# 32KRAM.net
KiCad netlist of a schematic drawn in EAGLE
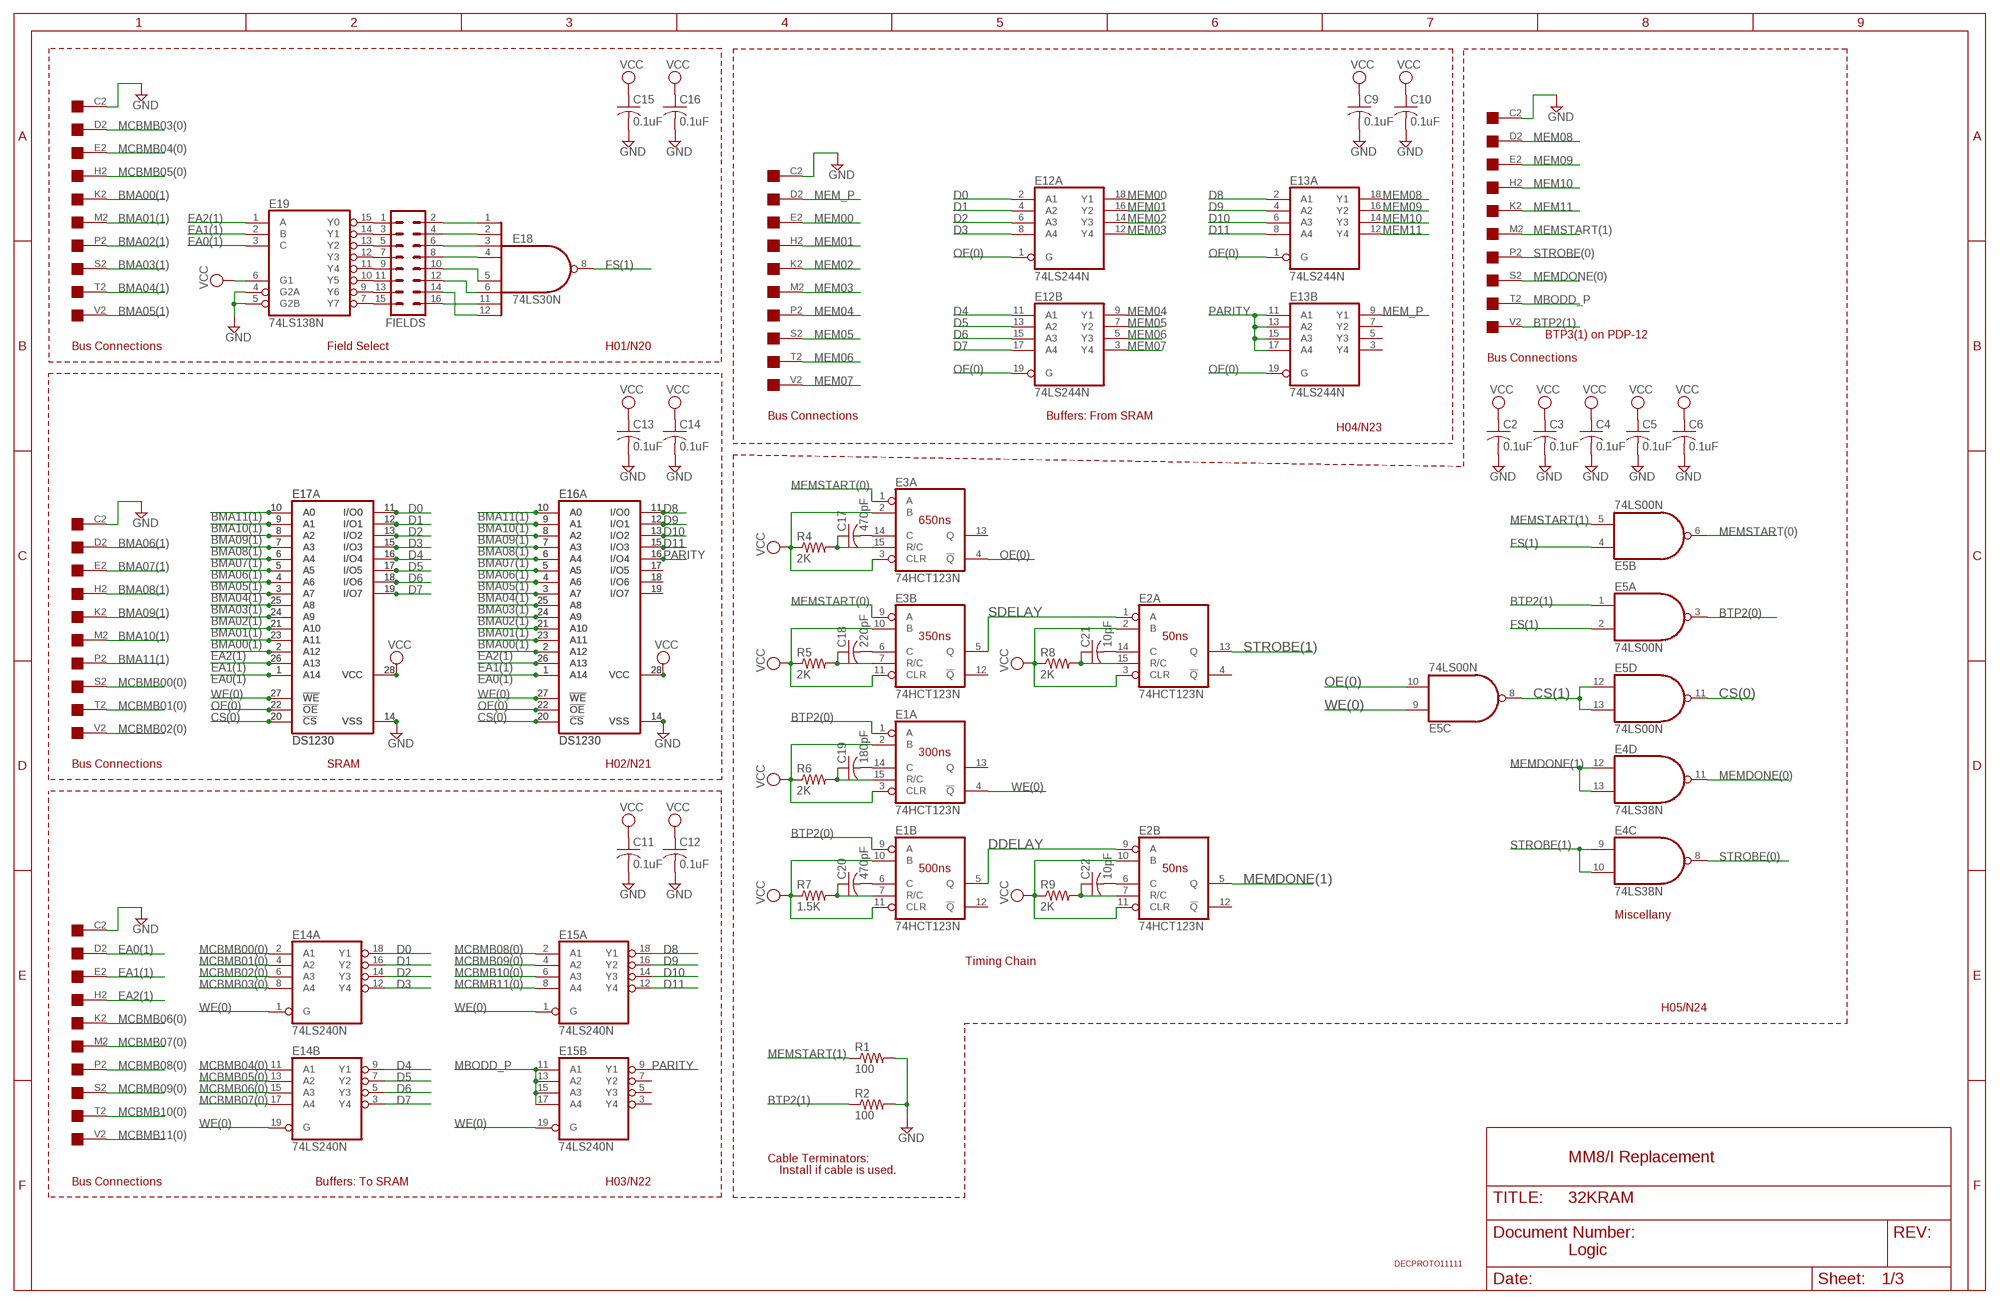
[diagram p0: schematic, sheet 1]
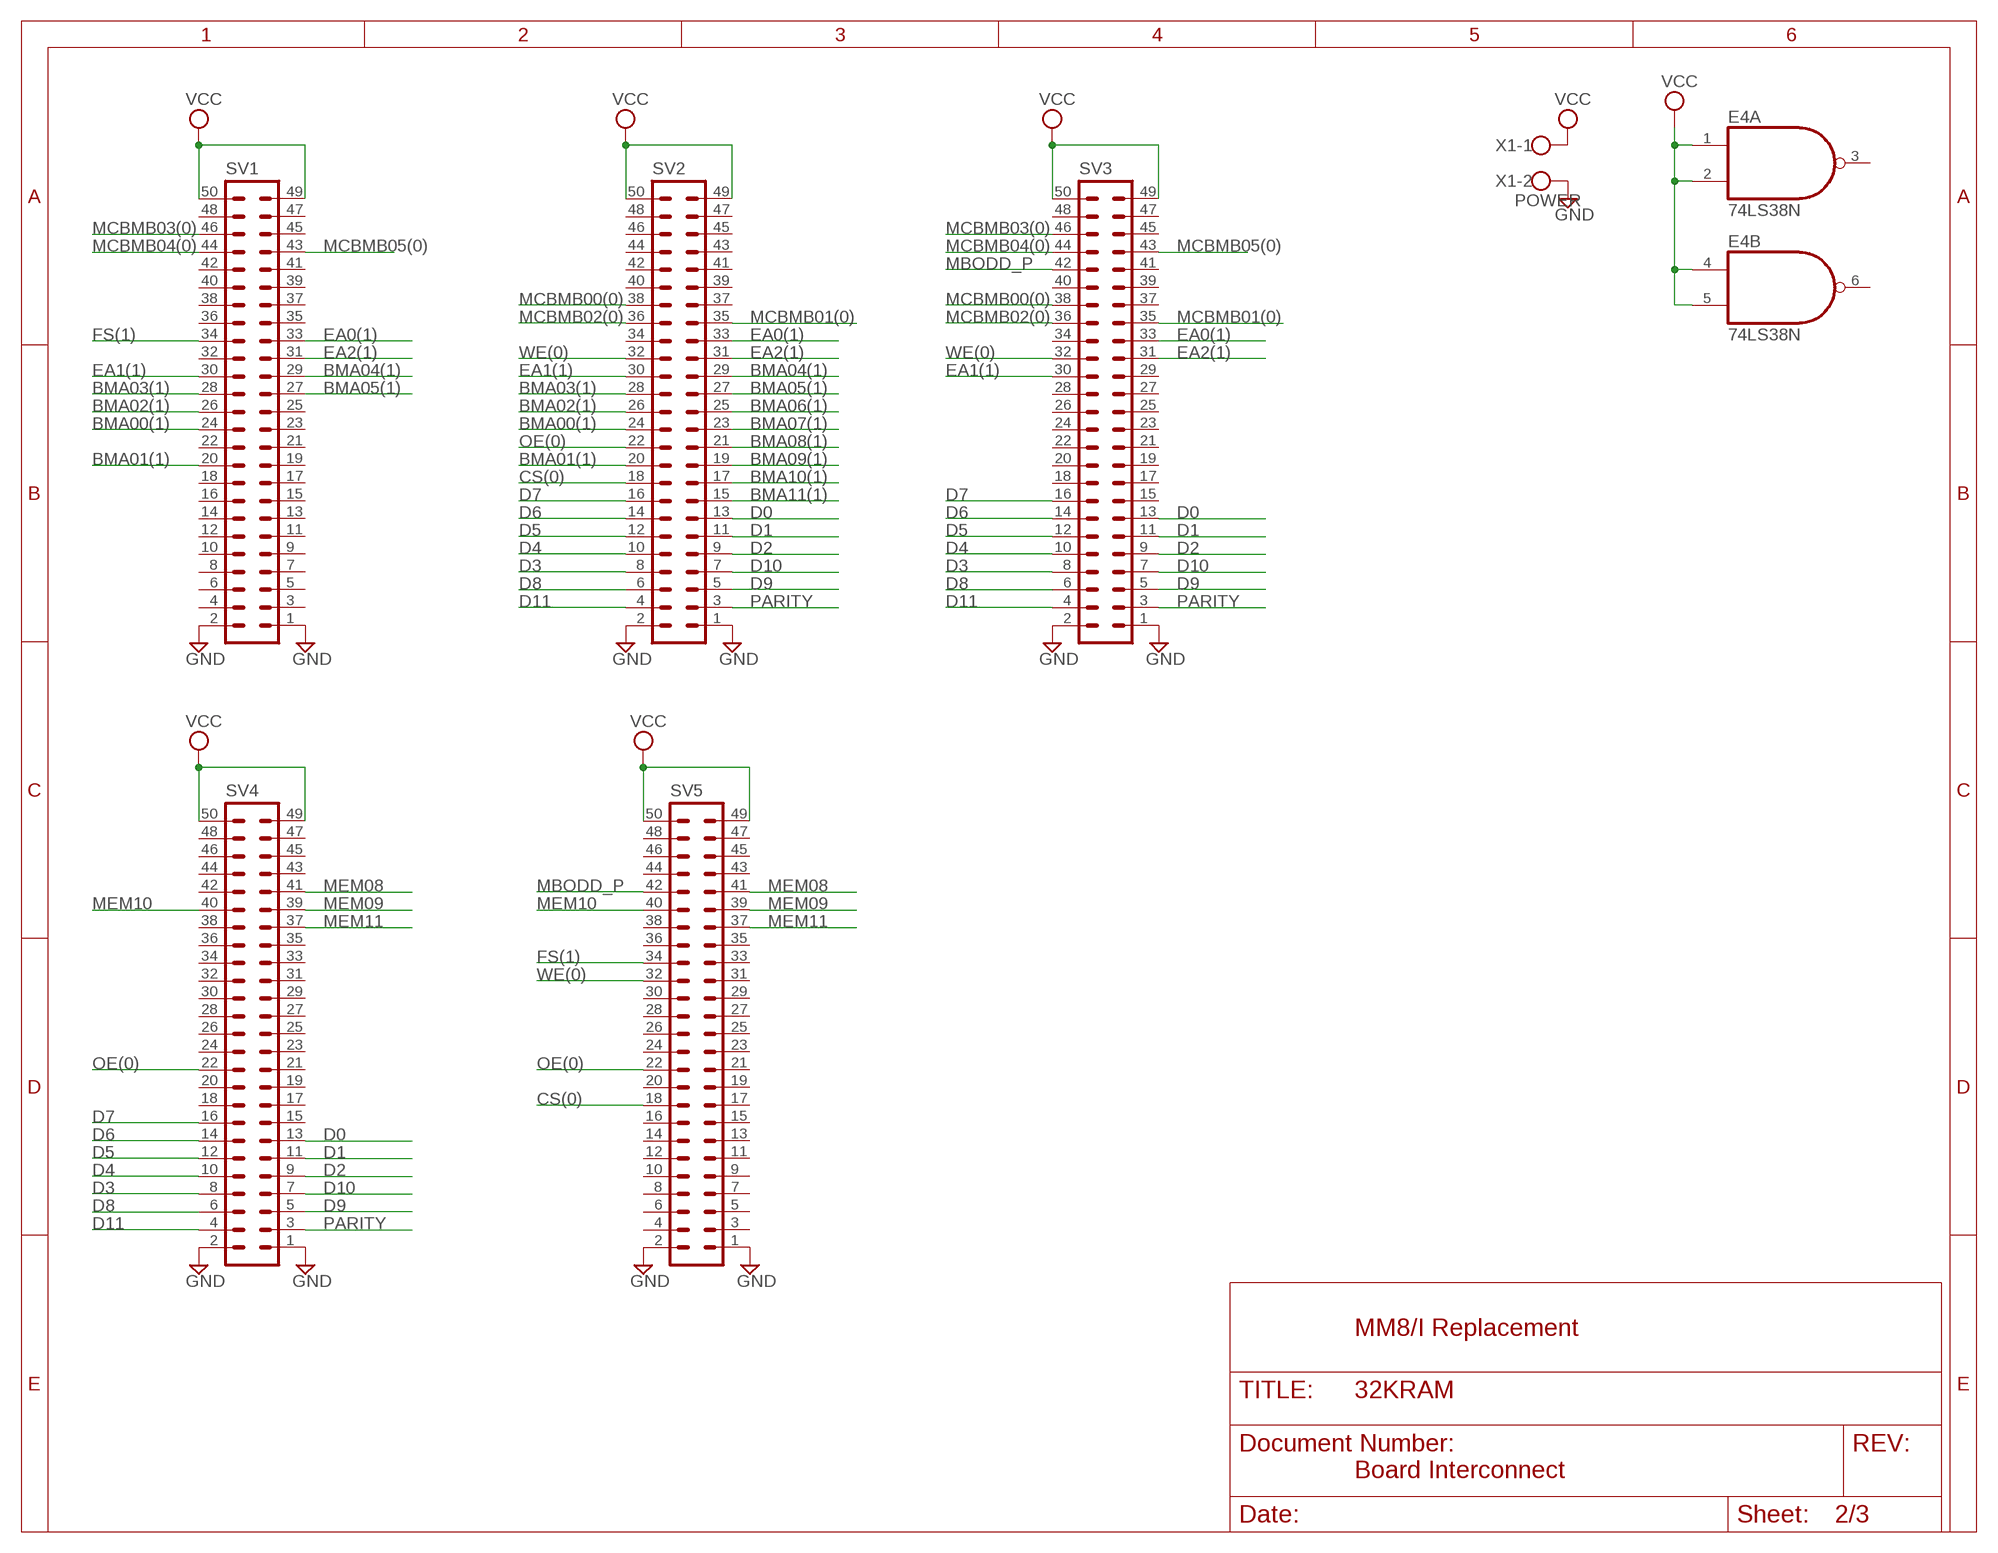
[diagram p1: schematic, sheet 2]
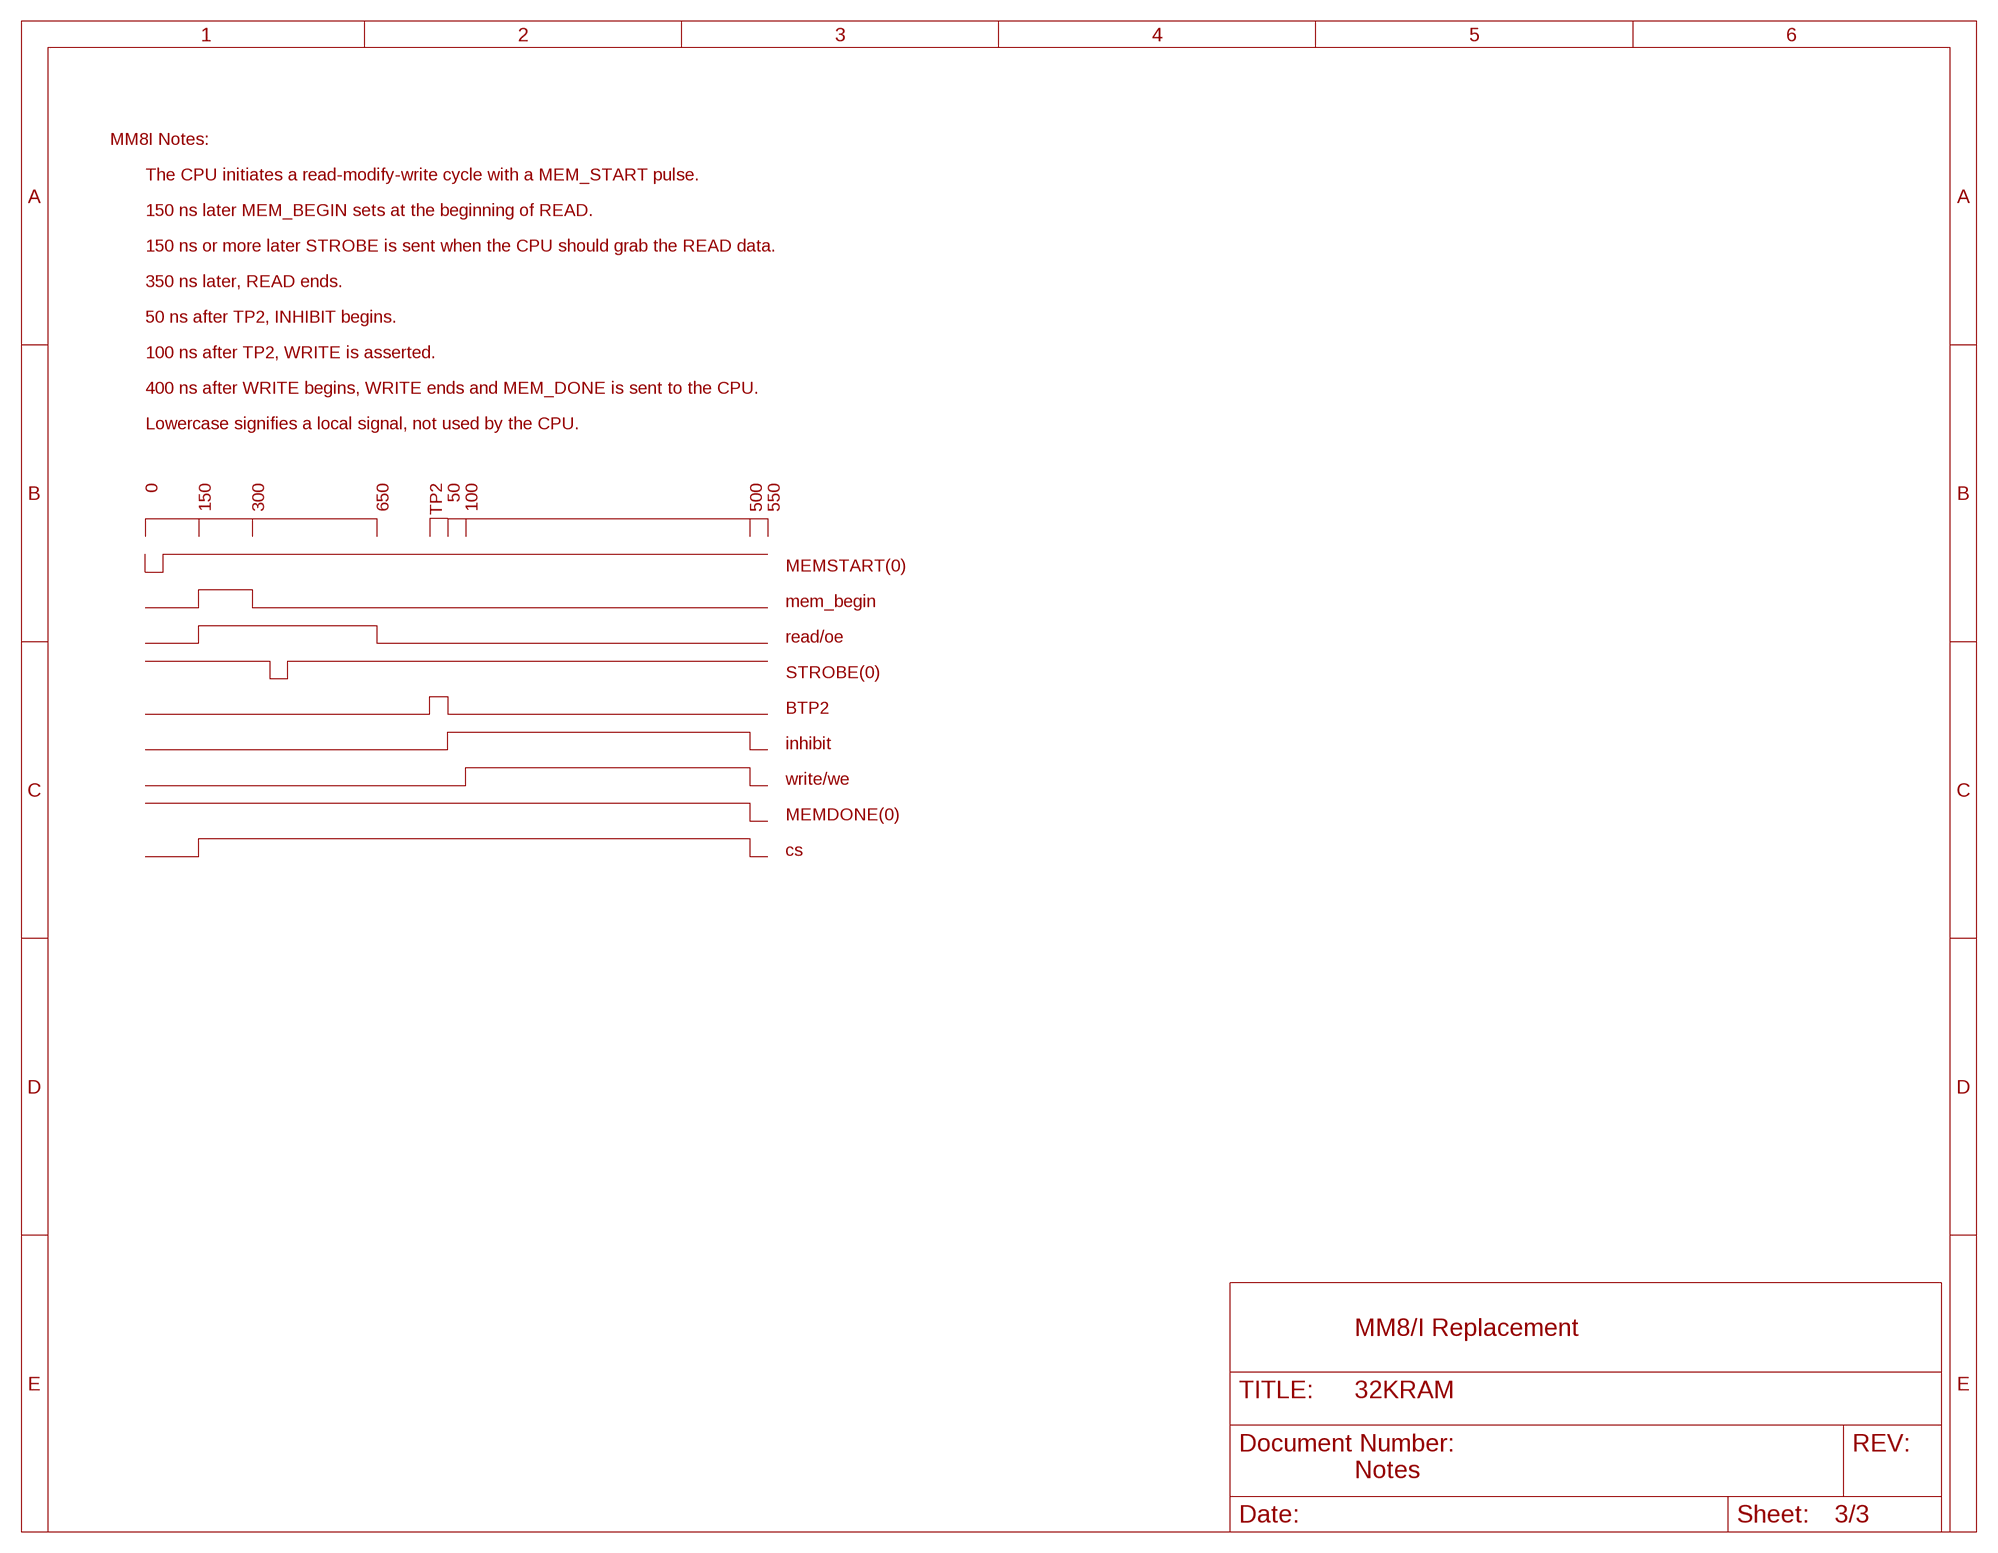
[diagram p2: schematic, sheet 3]

(export (version "E")
  (design (tool "Eeschema 10.0.6"))
  (components
    (comp (ref "E4")
      (value "74LS38N")
      (footprint "eagle-import:DIL14")
      (libsource (lib "eagle-import") (part "7438NLS"))
    )
    (comp (ref "SV1")
      (value "ML50L")
      (footprint "eagle-import:ML50L")
      (libsource (lib "eagle-import") (part "ML50L"))
    )
    (comp (ref "SV2")
      (value "ML50L")
      (footprint "eagle-import:ML50L")
      (libsource (lib "eagle-import") (part "ML50L"))
    )
    (comp (ref "SV3")
      (value "ML50L")
      (footprint "eagle-import:ML50L")
      (libsource (lib "eagle-import") (part "ML50L"))
    )
    (comp (ref "SV4")
      (value "ML50L")
      (footprint "eagle-import:ML50L")
      (libsource (lib "eagle-import") (part "ML50L"))
    )
    (comp (ref "SV5")
      (value "ML50L")
      (footprint "eagle-import:ML50L")
      (libsource (lib "eagle-import") (part "ML50L"))
    )
    (comp (ref "X1")
      (value "POWER")
      (footprint "eagle-import:W237-102")
      (fields (field (name "MPN") "237-102"))
      (libsource (lib "eagle-import") (part "W237-102"))
    )
    (comp (ref "C2")
      (value "0.1uF")
      (footprint "eagle-import:C050-025X075")
      (libsource (lib "eagle-import") (part "C-US050-025X075"))
    )
    (comp (ref "C3")
      (value "0.1uF")
      (footprint "eagle-import:C050-025X075")
      (libsource (lib "eagle-import") (part "C-US050-025X075"))
    )
    (comp (ref "C4")
      (value "0.1uF")
      (footprint "eagle-import:C050-025X075")
      (libsource (lib "eagle-import") (part "C-US050-025X075"))
    )
    (comp (ref "C5")
      (value "0.1uF")
      (footprint "eagle-import:C050-025X075")
      (libsource (lib "eagle-import") (part "C-US050-025X075"))
    )
    (comp (ref "C6")
      (value "0.1uF")
      (footprint "eagle-import:C050-025X075")
      (libsource (lib "eagle-import") (part "C-US050-025X075"))
    )
    (comp (ref "C9")
      (value "0.1uF")
      (footprint "eagle-import:C050-025X075")
      (libsource (lib "eagle-import") (part "C-US050-025X075"))
    )
    (comp (ref "C10")
      (value "0.1uF")
      (footprint "eagle-import:C050-025X075")
      (libsource (lib "eagle-import") (part "C-US050-025X075"))
    )
    (comp (ref "C11")
      (value "0.1uF")
      (footprint "eagle-import:C050-025X075")
      (libsource (lib "eagle-import") (part "C-US050-025X075"))
    )
    (comp (ref "C12")
      (value "0.1uF")
      (footprint "eagle-import:C050-025X075")
      (libsource (lib "eagle-import") (part "C-US050-025X075"))
    )
    (comp (ref "C13")
      (value "0.1uF")
      (footprint "eagle-import:C050-025X075")
      (libsource (lib "eagle-import") (part "C-US050-025X075"))
    )
    (comp (ref "C14")
      (value "0.1uF")
      (footprint "eagle-import:C050-025X075")
      (libsource (lib "eagle-import") (part "C-US050-025X075"))
    )
    (comp (ref "C15")
      (value "0.1uF")
      (footprint "eagle-import:C050-025X075")
      (libsource (lib "eagle-import") (part "C-US050-025X075"))
    )
    (comp (ref "C16")
      (value "0.1uF")
      (footprint "eagle-import:C050-025X075")
      (libsource (lib "eagle-import") (part "C-US050-025X075"))
    )
    (comp (ref "C17")
      (value "470pF")
      (footprint "eagle-import:C050-025X075")
      (libsource (lib "eagle-import") (part "C-US050-025X075"))
    )
    (comp (ref "C18")
      (value "220pF")
      (footprint "eagle-import:C050-025X075")
      (libsource (lib "eagle-import") (part "C-US050-025X075"))
    )
    (comp (ref "C19")
      (value "180pF")
      (footprint "eagle-import:C050-025X075")
      (libsource (lib "eagle-import") (part "C-US050-025X075"))
    )
    (comp (ref "C20")
      (value "470pF")
      (footprint "eagle-import:C050-025X075")
      (libsource (lib "eagle-import") (part "C-US050-025X075"))
    )
    (comp (ref "C21")
      (value "10pF")
      (footprint "eagle-import:C050-025X075")
      (libsource (lib "eagle-import") (part "C-US050-025X075"))
    )
    (comp (ref "C22")
      (value "10pF")
      (footprint "eagle-import:C050-025X075")
      (libsource (lib "eagle-import") (part "C-US050-025X075"))
    )
    (comp (ref "E1")
      (value "74HCT123N")
      (footprint "eagle-import:DIL16")
      (libsource (lib "eagle-import") (part "74123NLS"))
    )
    (comp (ref "E2")
      (value "74HCT123N")
      (footprint "eagle-import:DIL16")
      (libsource (lib "eagle-import") (part "74123NLS"))
    )
    (comp (ref "E3")
      (value "74HCT123N")
      (footprint "eagle-import:DIL16")
      (libsource (lib "eagle-import") (part "74123NLS"))
    )
    (comp (ref "E5")
      (value "74LS00N")
      (footprint "eagle-import:DIL14")
      (libsource (lib "eagle-import") (part "7400NLS"))
    )
    (comp (ref "E12")
      (value "74LS244N")
      (footprint "eagle-import:DIL20")
      (libsource (lib "eagle-import") (part "74244NS"))
    )
    (comp (ref "E13")
      (value "74LS244N")
      (footprint "eagle-import:DIL20")
      (libsource (lib "eagle-import") (part "74244NS"))
    )
    (comp (ref "E14")
      (value "74LS240N")
      (footprint "eagle-import:DIL20")
      (libsource (lib "eagle-import") (part "74240NS"))
    )
    (comp (ref "E15")
      (value "74LS240N")
      (footprint "eagle-import:DIL20")
      (libsource (lib "eagle-import") (part "74240NS"))
    )
    (comp (ref "E16")
      (value "DS1230")
      (footprint "eagle-import:DIL28-6")
      (libsource (lib "eagle-import") (part "62256P"))
    )
    (comp (ref "E16A")
      (value "DS1230")
      (footprint "eagle-import:DIL28-3")
      (libsource (lib "eagle-import") (part "62832P"))
    )
    (comp (ref "E17")
      (value "DS1230")
      (footprint "eagle-import:DIL28-6")
      (libsource (lib "eagle-import") (part "62256P"))
    )
    (comp (ref "E17A")
      (value "DS1230")
      (footprint "eagle-import:DIL28-3")
      (libsource (lib "eagle-import") (part "62832P"))
    )
    (comp (ref "E18")
      (value "74LS30N")
      (footprint "eagle-import:DIL14")
      (libsource (lib "eagle-import") (part "7430NLS"))
    )
    (comp (ref "E19")
      (value "74LS138N")
      (footprint "eagle-import:DIL16")
      (libsource (lib "eagle-import") (part "74138NLS"))
    )
    (comp (ref "FIELDS")
      (value "MA08-2")
      (footprint "eagle-import:MA08-2")
      (libsource (lib "eagle-import") (part "MA08-2"))
    )
    (comp (ref "H01")
      (value "EDGE-1")
      (footprint "eagle-import:EDGE-CON1")
      (libsource (lib "eagle-import") (part "EDGE-1"))
    )
    (comp (ref "H02")
      (value "EDGE-1")
      (footprint "eagle-import:EDGE-CON1")
      (libsource (lib "eagle-import") (part "EDGE-1"))
    )
    (comp (ref "H03")
      (value "EDGE-1")
      (footprint "eagle-import:EDGE-CON1")
      (libsource (lib "eagle-import") (part "EDGE-1"))
    )
    (comp (ref "H04")
      (value "EDGE-1")
      (footprint "eagle-import:EDGE-CON1")
      (libsource (lib "eagle-import") (part "EDGE-1"))
    )
    (comp (ref "H05")
      (value "EDGE-1")
      (footprint "eagle-import:EDGE-CON1")
      (libsource (lib "eagle-import") (part "EDGE-1"))
    )
    (comp (ref "R1")
      (value "100")
      (footprint "eagle-import:0207_10")
      (libsource (lib "eagle-import") (part "R-US_0207/10"))
    )
    (comp (ref "R2")
      (value "100")
      (footprint "eagle-import:0207_10")
      (libsource (lib "eagle-import") (part "R-US_0207/10"))
    )
    (comp (ref "R4")
      (value "2K")
      (footprint "eagle-import:0207_10")
      (libsource (lib "eagle-import") (part "R-US_0207/10"))
    )
    (comp (ref "R5")
      (value "2K")
      (footprint "eagle-import:0207_10")
      (libsource (lib "eagle-import") (part "R-US_0207/10"))
    )
    (comp (ref "R6")
      (value "2K")
      (footprint "eagle-import:0207_10")
      (libsource (lib "eagle-import") (part "R-US_0207/10"))
    )
    (comp (ref "R7")
      (value "1.5K")
      (footprint "eagle-import:0207_10")
      (libsource (lib "eagle-import") (part "R-US_0207/10"))
    )
    (comp (ref "R8")
      (value "2K")
      (footprint "eagle-import:0207_10")
      (libsource (lib "eagle-import") (part "R-US_0207/10"))
    )
    (comp (ref "R9")
      (value "2K")
      (footprint "eagle-import:0207_10")
      (libsource (lib "eagle-import") (part "R-US_0207/10"))
    )
    (comp (ref "U$6")
      (value "DECPROTO11111")
      (footprint "eagle-import:DECPROTO11111")
      (libsource (lib "eagle-import") (part "DECPROTO11111"))
    )
  )
  (nets
    (net (code "1") (name "BMA00(1)") (class "Default")
      (node (ref "E16") (pin "23") (pinfunction "A11_23") (pintype "input"))
      (node (ref "E16A") (pin "23") (pinfunction "A11_23") (pintype "input"))
      (node (ref "E17") (pin "23") (pinfunction "A11_23") (pintype "input"))
      (node (ref "E17A") (pin "23") (pinfunction "A11_23") (pintype "input"))
      (node (ref "H01") (pin "K2") (pinfunction "1_K2") (pintype "bidirectional"))
      (node (ref "SV1") (pin "24") (pinfunction "24_24") (pintype "passive"))
      (node (ref "SV2") (pin "24") (pinfunction "24_24") (pintype "passive"))
    )
    (net (code "2") (name "BMA01(1)") (class "Default")
      (node (ref "E16") (pin "21") (pinfunction "A10_21") (pintype "input"))
      (node (ref "E16A") (pin "21") (pinfunction "A10_21") (pintype "input"))
      (node (ref "E17") (pin "21") (pinfunction "A10_21") (pintype "input"))
      (node (ref "E17A") (pin "21") (pinfunction "A10_21") (pintype "input"))
      (node (ref "H01") (pin "M2") (pinfunction "1_M2") (pintype "bidirectional"))
      (node (ref "SV1") (pin "20") (pinfunction "20_20") (pintype "passive"))
      (node (ref "SV2") (pin "20") (pinfunction "20_20") (pintype "passive"))
    )
    (net (code "3") (name "BMA02(1)") (class "Default")
      (node (ref "E16") (pin "24") (pinfunction "A9_24") (pintype "input"))
      (node (ref "E16A") (pin "24") (pinfunction "A9_24") (pintype "input"))
      (node (ref "E17") (pin "24") (pinfunction "A9_24") (pintype "input"))
      (node (ref "E17A") (pin "24") (pinfunction "A9_24") (pintype "input"))
      (node (ref "H01") (pin "P2") (pinfunction "1_P2") (pintype "bidirectional"))
      (node (ref "SV1") (pin "26") (pinfunction "26_26") (pintype "passive"))
      (node (ref "SV2") (pin "26") (pinfunction "26_26") (pintype "passive"))
    )
    (net (code "4") (name "BMA03(1)") (class "Default")
      (node (ref "E16") (pin "25") (pinfunction "A8_25") (pintype "input"))
      (node (ref "E16A") (pin "25") (pinfunction "A8_25") (pintype "input"))
      (node (ref "E17") (pin "25") (pinfunction "A8_25") (pintype "input"))
      (node (ref "E17A") (pin "25") (pinfunction "A8_25") (pintype "input"))
      (node (ref "H01") (pin "S2") (pinfunction "1_S2") (pintype "bidirectional"))
      (node (ref "SV1") (pin "28") (pinfunction "28_28") (pintype "passive"))
      (node (ref "SV2") (pin "28") (pinfunction "28_28") (pintype "passive"))
    )
    (net (code "5") (name "BMA04(1)") (class "Default")
      (node (ref "E16") (pin "3") (pinfunction "A7_3") (pintype "input"))
      (node (ref "E16A") (pin "3") (pinfunction "A7_3") (pintype "input"))
      (node (ref "E17") (pin "3") (pinfunction "A7_3") (pintype "input"))
      (node (ref "E17A") (pin "3") (pinfunction "A7_3") (pintype "input"))
      (node (ref "H01") (pin "T2") (pinfunction "1_T2") (pintype "bidirectional"))
      (node (ref "SV1") (pin "29") (pinfunction "29_29") (pintype "passive"))
      (node (ref "SV2") (pin "29") (pinfunction "29_29") (pintype "passive"))
    )
    (net (code "6") (name "BMA05(1)") (class "Default")
      (node (ref "E16") (pin "4") (pinfunction "A6_4") (pintype "input"))
      (node (ref "E16A") (pin "4") (pinfunction "A6_4") (pintype "input"))
      (node (ref "E17") (pin "4") (pinfunction "A6_4") (pintype "input"))
      (node (ref "E17A") (pin "4") (pinfunction "A6_4") (pintype "input"))
      (node (ref "H01") (pin "V2") (pinfunction "1_V2") (pintype "bidirectional"))
      (node (ref "SV1") (pin "27") (pinfunction "27_27") (pintype "passive"))
      (node (ref "SV2") (pin "27") (pinfunction "27_27") (pintype "passive"))
    )
    (net (code "7") (name "BMA06(1)") (class "Default")
      (node (ref "E16") (pin "5") (pinfunction "A5_5") (pintype "input"))
      (node (ref "E16A") (pin "5") (pinfunction "A5_5") (pintype "input"))
      (node (ref "E17") (pin "5") (pinfunction "A5_5") (pintype "input"))
      (node (ref "E17A") (pin "5") (pinfunction "A5_5") (pintype "input"))
      (node (ref "H02") (pin "D2") (pinfunction "1_D2") (pintype "bidirectional"))
      (node (ref "SV2") (pin "25") (pinfunction "25_25") (pintype "passive"))
    )
    (net (code "8") (name "BMA07(1)") (class "Default")
      (node (ref "E16") (pin "6") (pinfunction "A4_6") (pintype "input"))
      (node (ref "E16A") (pin "6") (pinfunction "A4_6") (pintype "input"))
      (node (ref "E17") (pin "6") (pinfunction "A4_6") (pintype "input"))
      (node (ref "E17A") (pin "6") (pinfunction "A4_6") (pintype "input"))
      (node (ref "H02") (pin "E2") (pinfunction "1_E2") (pintype "bidirectional"))
      (node (ref "SV2") (pin "23") (pinfunction "23_23") (pintype "passive"))
    )
    (net (code "9") (name "BMA08(1)") (class "Default")
      (node (ref "E16") (pin "7") (pinfunction "A3_7") (pintype "input"))
      (node (ref "E16A") (pin "7") (pinfunction "A3_7") (pintype "input"))
      (node (ref "E17") (pin "7") (pinfunction "A3_7") (pintype "input"))
      (node (ref "E17A") (pin "7") (pinfunction "A3_7") (pintype "input"))
      (node (ref "H02") (pin "H2") (pinfunction "1_H2") (pintype "bidirectional"))
      (node (ref "SV2") (pin "21") (pinfunction "21_21") (pintype "passive"))
    )
    (net (code "10") (name "BMA09(1)") (class "Default")
      (node (ref "E16") (pin "8") (pinfunction "A2_8") (pintype "input"))
      (node (ref "E16A") (pin "8") (pinfunction "A2_8") (pintype "input"))
      (node (ref "E17") (pin "8") (pinfunction "A2_8") (pintype "input"))
      (node (ref "E17A") (pin "8") (pinfunction "A2_8") (pintype "input"))
      (node (ref "H02") (pin "K2") (pinfunction "1_K2") (pintype "bidirectional"))
      (node (ref "SV2") (pin "19") (pinfunction "19_19") (pintype "passive"))
    )
    (net (code "11") (name "BMA10(1)") (class "Default")
      (node (ref "E16") (pin "9") (pinfunction "A1_9") (pintype "input"))
      (node (ref "E16A") (pin "9") (pinfunction "A1_9") (pintype "input"))
      (node (ref "E17") (pin "9") (pinfunction "A1_9") (pintype "input"))
      (node (ref "E17A") (pin "9") (pinfunction "A1_9") (pintype "input"))
      (node (ref "H02") (pin "M2") (pinfunction "1_M2") (pintype "bidirectional"))
      (node (ref "SV2") (pin "17") (pinfunction "17_17") (pintype "passive"))
    )
    (net (code "12") (name "BMA11(1)") (class "Default")
      (node (ref "E16") (pin "10") (pinfunction "A0_10") (pintype "input"))
      (node (ref "E16A") (pin "10") (pinfunction "A0_10") (pintype "input"))
      (node (ref "E17") (pin "10") (pinfunction "A0_10") (pintype "input"))
      (node (ref "E17A") (pin "10") (pinfunction "A0_10") (pintype "input"))
      (node (ref "H02") (pin "P2") (pinfunction "1_P2") (pintype "bidirectional"))
      (node (ref "SV2") (pin "15") (pinfunction "15_15") (pintype "passive"))
    )
    (net (code "13") (name "BTP2(0)") (class "Default")
      (node (ref "E1") (pin "1") (pinfunction "A_1") (pintype "input"))
      (node (ref "E1") (pin "9") (pinfunction "A_9") (pintype "input"))
      (node (ref "E5") (pin "3") (pinfunction "O_3") (pintype "output"))
    )
    (net (code "14") (name "BTP2(1)") (class "Default")
      (node (ref "E5") (pin "1") (pinfunction "I0_1") (pintype "input"))
      (node (ref "H05") (pin "V2") (pinfunction "1_V2") (pintype "bidirectional"))
      (node (ref "R2") (pin "1") (pinfunction "1_1") (pintype "passive"))
    )
    (net (code "15") (name "CS(0)") (class "Default")
      (node (ref "E16") (pin "20") (pinfunction "~{CS}_20") (pintype "input"))
      (node (ref "E16A") (pin "20") (pinfunction "~{CS}_20") (pintype "input"))
      (node (ref "E17") (pin "20") (pinfunction "~{CS}_20") (pintype "input"))
      (node (ref "E17A") (pin "20") (pinfunction "~{CS}_20") (pintype "input"))
      (node (ref "E5") (pin "11") (pinfunction "O_11") (pintype "output"))
      (node (ref "SV2") (pin "18") (pinfunction "18_18") (pintype "passive"))
      (node (ref "SV5") (pin "18") (pinfunction "18_18") (pintype "passive"))
    )
    (net (code "16") (name "CS(1)") (class "Default")
      (node (ref "E5") (pin "12") (pinfunction "I0_12") (pintype "input"))
      (node (ref "E5") (pin "13") (pinfunction "I1_13") (pintype "input"))
      (node (ref "E5") (pin "8") (pinfunction "O_8") (pintype "output"))
    )
    (net (code "17") (name "D0") (class "Default")
      (node (ref "E12") (pin "2") (pinfunction "A1_2") (pintype "input"))
      (node (ref "E14") (pin "18") (pinfunction "Y1_18") (pintype "tri_state"))
      (node (ref "E17") (pin "11") (pinfunction "I/O0_11") (pintype "bidirectional"))
      (node (ref "E17A") (pin "11") (pinfunction "I/O0_11") (pintype "bidirectional"))
      (node (ref "SV2") (pin "13") (pinfunction "13_13") (pintype "passive"))
      (node (ref "SV3") (pin "13") (pinfunction "13_13") (pintype "passive"))
      (node (ref "SV4") (pin "13") (pinfunction "13_13") (pintype "passive"))
    )
    (net (code "18") (name "D1") (class "Default")
      (node (ref "E12") (pin "4") (pinfunction "A2_4") (pintype "input"))
      (node (ref "E14") (pin "16") (pinfunction "Y2_16") (pintype "tri_state"))
      (node (ref "E17") (pin "12") (pinfunction "I/O1_12") (pintype "bidirectional"))
      (node (ref "E17A") (pin "12") (pinfunction "I/O1_12") (pintype "bidirectional"))
      (node (ref "SV2") (pin "11") (pinfunction "11_11") (pintype "passive"))
      (node (ref "SV3") (pin "11") (pinfunction "11_11") (pintype "passive"))
      (node (ref "SV4") (pin "11") (pinfunction "11_11") (pintype "passive"))
    )
    (net (code "19") (name "D2") (class "Default")
      (node (ref "E12") (pin "6") (pinfunction "A3_6") (pintype "input"))
      (node (ref "E14") (pin "14") (pinfunction "Y3_14") (pintype "tri_state"))
      (node (ref "E17") (pin "13") (pinfunction "I/O2_13") (pintype "bidirectional"))
      (node (ref "E17A") (pin "13") (pinfunction "I/O2_13") (pintype "bidirectional"))
      (node (ref "SV2") (pin "9") (pinfunction "9_9") (pintype "passive"))
      (node (ref "SV3") (pin "9") (pinfunction "9_9") (pintype "passive"))
      (node (ref "SV4") (pin "9") (pinfunction "9_9") (pintype "passive"))
    )
    (net (code "20") (name "D3") (class "Default")
      (node (ref "E12") (pin "8") (pinfunction "A4_8") (pintype "input"))
      (node (ref "E14") (pin "12") (pinfunction "Y4_12") (pintype "tri_state"))
      (node (ref "E17") (pin "15") (pinfunction "I/O3_15") (pintype "bidirectional"))
      (node (ref "E17A") (pin "15") (pinfunction "I/O3_15") (pintype "bidirectional"))
      (node (ref "SV2") (pin "8") (pinfunction "8_8") (pintype "passive"))
      (node (ref "SV3") (pin "8") (pinfunction "8_8") (pintype "passive"))
      (node (ref "SV4") (pin "8") (pinfunction "8_8") (pintype "passive"))
    )
    (net (code "21") (name "D4") (class "Default")
      (node (ref "E12") (pin "11") (pinfunction "A1_11") (pintype "input"))
      (node (ref "E14") (pin "9") (pinfunction "Y1_9") (pintype "tri_state"))
      (node (ref "E17") (pin "16") (pinfunction "I/O4_16") (pintype "bidirectional"))
      (node (ref "E17A") (pin "16") (pinfunction "I/O4_16") (pintype "bidirectional"))
      (node (ref "SV2") (pin "10") (pinfunction "10_10") (pintype "passive"))
      (node (ref "SV3") (pin "10") (pinfunction "10_10") (pintype "passive"))
      (node (ref "SV4") (pin "10") (pinfunction "10_10") (pintype "passive"))
    )
    (net (code "22") (name "D5") (class "Default")
      (node (ref "E12") (pin "13") (pinfunction "A2_13") (pintype "input"))
      (node (ref "E14") (pin "7") (pinfunction "Y2_7") (pintype "tri_state"))
      (node (ref "E17") (pin "17") (pinfunction "I/O5_17") (pintype "bidirectional"))
      (node (ref "E17A") (pin "17") (pinfunction "I/O5_17") (pintype "bidirectional"))
      (node (ref "SV2") (pin "12") (pinfunction "12_12") (pintype "passive"))
      (node (ref "SV3") (pin "12") (pinfunction "12_12") (pintype "passive"))
      (node (ref "SV4") (pin "12") (pinfunction "12_12") (pintype "passive"))
    )
    (net (code "23") (name "D6") (class "Default")
      (node (ref "E12") (pin "15") (pinfunction "A3_15") (pintype "input"))
      (node (ref "E14") (pin "5") (pinfunction "Y3_5") (pintype "tri_state"))
      (node (ref "E17") (pin "18") (pinfunction "I/O6_18") (pintype "bidirectional"))
      (node (ref "E17A") (pin "18") (pinfunction "I/O6_18") (pintype "bidirectional"))
      (node (ref "SV2") (pin "14") (pinfunction "14_14") (pintype "passive"))
      (node (ref "SV3") (pin "14") (pinfunction "14_14") (pintype "passive"))
      (node (ref "SV4") (pin "14") (pinfunction "14_14") (pintype "passive"))
    )
    (net (code "24") (name "D7") (class "Default")
      (node (ref "E12") (pin "17") (pinfunction "A4_17") (pintype "input"))
      (node (ref "E14") (pin "3") (pinfunction "Y4_3") (pintype "tri_state"))
      (node (ref "E17") (pin "19") (pinfunction "I/O7_19") (pintype "bidirectional"))
      (node (ref "E17A") (pin "19") (pinfunction "I/O7_19") (pintype "bidirectional"))
      (node (ref "SV2") (pin "16") (pinfunction "16_16") (pintype "passive"))
      (node (ref "SV3") (pin "16") (pinfunction "16_16") (pintype "passive"))
      (node (ref "SV4") (pin "16") (pinfunction "16_16") (pintype "passive"))
    )
    (net (code "25") (name "D8") (class "Default")
      (node (ref "E13") (pin "2") (pinfunction "A1_2") (pintype "input"))
      (node (ref "E15") (pin "18") (pinfunction "Y1_18") (pintype "tri_state"))
      (node (ref "E16") (pin "11") (pinfunction "I/O0_11") (pintype "bidirectional"))
      (node (ref "E16A") (pin "11") (pinfunction "I/O0_11") (pintype "bidirectional"))
      (node (ref "SV2") (pin "6") (pinfunction "6_6") (pintype "passive"))
      (node (ref "SV3") (pin "6") (pinfunction "6_6") (pintype "passive"))
      (node (ref "SV4") (pin "6") (pinfunction "6_6") (pintype "passive"))
    )
    (net (code "26") (name "D9") (class "Default")
      (node (ref "E13") (pin "4") (pinfunction "A2_4") (pintype "input"))
      (node (ref "E15") (pin "16") (pinfunction "Y2_16") (pintype "tri_state"))
      (node (ref "E16") (pin "12") (pinfunction "I/O1_12") (pintype "bidirectional"))
      (node (ref "E16A") (pin "12") (pinfunction "I/O1_12") (pintype "bidirectional"))
      (node (ref "SV2") (pin "5") (pinfunction "5_5") (pintype "passive"))
      (node (ref "SV3") (pin "5") (pinfunction "5_5") (pintype "passive"))
      (node (ref "SV4") (pin "5") (pinfunction "5_5") (pintype "passive"))
    )
    (net (code "27") (name "D10") (class "Default")
      (node (ref "E13") (pin "6") (pinfunction "A3_6") (pintype "input"))
      (node (ref "E15") (pin "14") (pinfunction "Y3_14") (pintype "tri_state"))
      (node (ref "E16") (pin "13") (pinfunction "I/O2_13") (pintype "bidirectional"))
      (node (ref "E16A") (pin "13") (pinfunction "I/O2_13") (pintype "bidirectional"))
      (node (ref "SV2") (pin "7") (pinfunction "7_7") (pintype "passive"))
      (node (ref "SV3") (pin "7") (pinfunction "7_7") (pintype "passive"))
      (node (ref "SV4") (pin "7") (pinfunction "7_7") (pintype "passive"))
    )
    (net (code "28") (name "D11") (class "Default")
      (node (ref "E13") (pin "8") (pinfunction "A4_8") (pintype "input"))
      (node (ref "E15") (pin "12") (pinfunction "Y4_12") (pintype "tri_state"))
      (node (ref "E16") (pin "15") (pinfunction "I/O3_15") (pintype "bidirectional"))
      (node (ref "E16A") (pin "15") (pinfunction "I/O3_15") (pintype "bidirectional"))
      (node (ref "SV2") (pin "4") (pinfunction "4_4") (pintype "passive"))
      (node (ref "SV3") (pin "4") (pinfunction "4_4") (pintype "passive"))
      (node (ref "SV4") (pin "4") (pinfunction "4_4") (pintype "passive"))
    )
    (net (code "29") (name "DDELAY") (class "Default")
      (node (ref "E1") (pin "5") (pinfunction "Q_5") (pintype "output"))
      (node (ref "E2") (pin "9") (pinfunction "A_9") (pintype "input"))
    )
    (net (code "30") (name "EA0(1)") (class "Default")
      (node (ref "E16") (pin "1") (pinfunction "A14_1") (pintype "input"))
      (node (ref "E16A") (pin "1") (pinfunction "A14_1") (pintype "input"))
      (node (ref "E17") (pin "1") (pinfunction "A14_1") (pintype "input"))
      (node (ref "E17A") (pin "1") (pinfunction "A14_1") (pintype "input"))
      (node (ref "E19") (pin "3") (pinfunction "C_3") (pintype "input"))
      (node (ref "H03") (pin "D2") (pinfunction "1_D2") (pintype "bidirectional"))
      (node (ref "SV1") (pin "33") (pinfunction "33_33") (pintype "passive"))
      (node (ref "SV2") (pin "33") (pinfunction "33_33") (pintype "passive"))
      (node (ref "SV3") (pin "33") (pinfunction "33_33") (pintype "passive"))
    )
    (net (code "31") (name "EA1(1)") (class "Default")
      (node (ref "E16") (pin "26") (pinfunction "A13_26") (pintype "input"))
      (node (ref "E16A") (pin "26") (pinfunction "A13_26") (pintype "input"))
      (node (ref "E17") (pin "26") (pinfunction "A13_26") (pintype "input"))
      (node (ref "E17A") (pin "26") (pinfunction "A13_26") (pintype "input"))
      (node (ref "E19") (pin "2") (pinfunction "B_2") (pintype "input"))
      (node (ref "H03") (pin "E2") (pinfunction "1_E2") (pintype "bidirectional"))
      (node (ref "SV1") (pin "30") (pinfunction "30_30") (pintype "passive"))
      (node (ref "SV2") (pin "30") (pinfunction "30_30") (pintype "passive"))
      (node (ref "SV3") (pin "30") (pinfunction "30_30") (pintype "passive"))
    )
    (net (code "32") (name "EA2(1)") (class "Default")
      (node (ref "E16") (pin "2") (pinfunction "A12_2") (pintype "input"))
      (node (ref "E16A") (pin "2") (pinfunction "A12_2") (pintype "input"))
      (node (ref "E17") (pin "2") (pinfunction "A12_2") (pintype "input"))
      (node (ref "E17A") (pin "2") (pinfunction "A12_2") (pintype "input"))
      (node (ref "E19") (pin "1") (pinfunction "A_1") (pintype "input"))
      (node (ref "H03") (pin "H2") (pinfunction "1_H2") (pintype "bidirectional"))
      (node (ref "SV1") (pin "31") (pinfunction "31_31") (pintype "passive"))
      (node (ref "SV2") (pin "31") (pinfunction "31_31") (pintype "passive"))
      (node (ref "SV3") (pin "31") (pinfunction "31_31") (pintype "passive"))
    )
    (net (code "33") (name "FS(1)") (class "Default")
      (node (ref "E18") (pin "8") (pinfunction "O_8") (pintype "output"))
      (node (ref "E5") (pin "2") (pinfunction "I1_2") (pintype "input"))
      (node (ref "E5") (pin "4") (pinfunction "I0_4") (pintype "input"))
      (node (ref "SV1") (pin "34") (pinfunction "34_34") (pintype "passive"))
      (node (ref "SV5") (pin "34") (pinfunction "34_34") (pintype "passive"))
    )
    (net (code "34") (name "GND") (class "Default")
      (node (ref "C10") (pin "2") (pinfunction "2_2") (pintype "passive"))
      (node (ref "C11") (pin "2") (pinfunction "2_2") (pintype "passive"))
      (node (ref "C12") (pin "2") (pinfunction "2_2") (pintype "passive"))
      (node (ref "C13") (pin "2") (pinfunction "2_2") (pintype "passive"))
      (node (ref "C14") (pin "2") (pinfunction "2_2") (pintype "passive"))
      (node (ref "C15") (pin "2") (pinfunction "2_2") (pintype "passive"))
      (node (ref "C16") (pin "2") (pinfunction "2_2") (pintype "passive"))
      (node (ref "C2") (pin "2") (pinfunction "2_2") (pintype "passive"))
      (node (ref "C3") (pin "2") (pinfunction "2_2") (pintype "passive"))
      (node (ref "C4") (pin "2") (pinfunction "2_2") (pintype "passive"))
      (node (ref "C5") (pin "2") (pinfunction "2_2") (pintype "passive"))
      (node (ref "C6") (pin "2") (pinfunction "2_2") (pintype "passive"))
      (node (ref "C9") (pin "2") (pinfunction "2_2") (pintype "passive"))
      (node (ref "E16") (pin "14") (pinfunction "VSS_14") (pintype "power_in"))
      (node (ref "E16A") (pin "14") (pinfunction "VSS_14") (pintype "power_in"))
      (node (ref "E17") (pin "14") (pinfunction "VSS_14") (pintype "power_in"))
      (node (ref "E17A") (pin "14") (pinfunction "VSS_14") (pintype "power_in"))
      (node (ref "E19") (pin "4") (pinfunction "G2A_4") (pintype "input"))
      (node (ref "E19") (pin "5") (pinfunction "G2B_5") (pintype "input"))
      (node (ref "H01") (pin "C2") (pinfunction "1_C2") (pintype "bidirectional"))
      (node (ref "H02") (pin "C2") (pinfunction "1_C2") (pintype "bidirectional"))
      (node (ref "H03") (pin "C2") (pinfunction "1_C2") (pintype "bidirectional"))
      (node (ref "H04") (pin "C2") (pinfunction "1_C2") (pintype "bidirectional"))
      (node (ref "H05") (pin "C2") (pinfunction "1_C2") (pintype "bidirectional"))
      (node (ref "R1") (pin "2") (pinfunction "2_2") (pintype "passive"))
      (node (ref "R2") (pin "2") (pinfunction "2_2") (pintype "passive"))
      (node (ref "SV1") (pin "1") (pinfunction "1_1") (pintype "passive"))
      (node (ref "SV1") (pin "2") (pinfunction "2_2") (pintype "passive"))
      (node (ref "SV2") (pin "1") (pinfunction "1_1") (pintype "passive"))
      (node (ref "SV2") (pin "2") (pinfunction "2_2") (pintype "passive"))
      (node (ref "SV3") (pin "1") (pinfunction "1_1") (pintype "passive"))
      (node (ref "SV3") (pin "2") (pinfunction "2_2") (pintype "passive"))
      (node (ref "SV4") (pin "1") (pinfunction "1_1") (pintype "passive"))
      (node (ref "SV4") (pin "2") (pinfunction "2_2") (pintype "passive"))
      (node (ref "SV5") (pin "1") (pinfunction "1_1") (pintype "passive"))
      (node (ref "SV5") (pin "2") (pinfunction "2_2") (pintype "passive"))
      (node (ref "X1") (pin "2") (pinfunction "KL_2") (pintype "passive"))
    )
    (net (code "35") (name "MBODD_P") (class "Default")
      (node (ref "E15") (pin "11") (pinfunction "A1_11") (pintype "input"))
      (node (ref "E15") (pin "13") (pinfunction "A2_13") (pintype "input"))
      (node (ref "E15") (pin "15") (pinfunction "A3_15") (pintype "input"))
      (node (ref "E15") (pin "17") (pinfunction "A4_17") (pintype "input"))
      (node (ref "H05") (pin "T2") (pinfunction "1_T2") (pintype "bidirectional"))
      (node (ref "SV3") (pin "42") (pinfunction "42_42") (pintype "passive"))
      (node (ref "SV5") (pin "42") (pinfunction "42_42") (pintype "passive"))
    )
    (net (code "36") (name "MCBMB00(0)") (class "Default")
      (node (ref "E14") (pin "2") (pinfunction "A1_2") (pintype "input"))
      (node (ref "H02") (pin "S2") (pinfunction "1_S2") (pintype "bidirectional"))
      (node (ref "SV2") (pin "38") (pinfunction "38_38") (pintype "passive"))
      (node (ref "SV3") (pin "38") (pinfunction "38_38") (pintype "passive"))
    )
    (net (code "37") (name "MCBMB01(0)") (class "Default")
      (node (ref "E14") (pin "4") (pinfunction "A2_4") (pintype "input"))
      (node (ref "H02") (pin "T2") (pinfunction "1_T2") (pintype "bidirectional"))
      (node (ref "SV2") (pin "35") (pinfunction "35_35") (pintype "passive"))
      (node (ref "SV3") (pin "35") (pinfunction "35_35") (pintype "passive"))
    )
    (net (code "38") (name "MCBMB02(0)") (class "Default")
      (node (ref "E14") (pin "6") (pinfunction "A3_6") (pintype "input"))
      (node (ref "H02") (pin "V2") (pinfunction "1_V2") (pintype "bidirectional"))
      (node (ref "SV2") (pin "36") (pinfunction "36_36") (pintype "passive"))
      (node (ref "SV3") (pin "36") (pinfunction "36_36") (pintype "passive"))
    )
    (net (code "39") (name "MCBMB03(0)") (class "Default")
      (node (ref "E14") (pin "8") (pinfunction "A4_8") (pintype "input"))
      (node (ref "H01") (pin "D2") (pinfunction "1_D2") (pintype "bidirectional"))
      (node (ref "SV1") (pin "46") (pinfunction "46_46") (pintype "passive"))
      (node (ref "SV3") (pin "46") (pinfunction "46_46") (pintype "passive"))
    )
    (net (code "40") (name "MCBMB04(0)") (class "Default")
      (node (ref "E14") (pin "11") (pinfunction "A1_11") (pintype "input"))
      (node (ref "H01") (pin "E2") (pinfunction "1_E2") (pintype "bidirectional"))
      (node (ref "SV1") (pin "44") (pinfunction "44_44") (pintype "passive"))
      (node (ref "SV3") (pin "44") (pinfunction "44_44") (pintype "passive"))
    )
    (net (code "41") (name "MCBMB05(0)") (class "Default")
      (node (ref "E14") (pin "13") (pinfunction "A2_13") (pintype "input"))
      (node (ref "H01") (pin "H2") (pinfunction "1_H2") (pintype "bidirectional"))
      (node (ref "SV1") (pin "43") (pinfunction "43_43") (pintype "passive"))
      (node (ref "SV3") (pin "43") (pinfunction "43_43") (pintype "passive"))
    )
    (net (code "42") (name "MCBMB06(0)") (class "Default")
      (node (ref "E14") (pin "15") (pinfunction "A3_15") (pintype "input"))
      (node (ref "H03") (pin "K2") (pinfunction "1_K2") (pintype "bidirectional"))
    )
    (net (code "43") (name "MCBMB07(0)") (class "Default")
      (node (ref "E14") (pin "17") (pinfunction "A4_17") (pintype "input"))
      (node (ref "H03") (pin "M2") (pinfunction "1_M2") (pintype "bidirectional"))
    )
    (net (code "44") (name "MCBMB08(0)") (class "Default")
      (node (ref "E15") (pin "2") (pinfunction "A1_2") (pintype "input"))
      (node (ref "H03") (pin "P2") (pinfunction "1_P2") (pintype "bidirectional"))
    )
    (net (code "45") (name "MCBMB09(0)") (class "Default")
      (node (ref "E15") (pin "4") (pinfunction "A2_4") (pintype "input"))
      (node (ref "H03") (pin "S2") (pinfunction "1_S2") (pintype "bidirectional"))
    )
    (net (code "46") (name "MCBMB10(0)") (class "Default")
      (node (ref "E15") (pin "6") (pinfunction "A3_6") (pintype "input"))
      (node (ref "H03") (pin "T2") (pinfunction "1_T2") (pintype "bidirectional"))
    )
    (net (code "47") (name "MCBMB11(0)") (class "Default")
      (node (ref "E15") (pin "8") (pinfunction "A4_8") (pintype "input"))
      (node (ref "H03") (pin "V2") (pinfunction "1_V2") (pintype "bidirectional"))
    )
    (net (code "48") (name "MEM00") (class "Default")
      (node (ref "E12") (pin "18") (pinfunction "Y1_18") (pintype "tri_state"))
      (node (ref "H04") (pin "E2") (pinfunction "1_E2") (pintype "bidirectional"))
    )
    (net (code "49") (name "MEM01") (class "Default")
      (node (ref "E12") (pin "16") (pinfunction "Y2_16") (pintype "tri_state"))
      (node (ref "H04") (pin "H2") (pinfunction "1_H2") (pintype "bidirectional"))
    )
    (net (code "50") (name "MEM02") (class "Default")
      (node (ref "E12") (pin "14") (pinfunction "Y3_14") (pintype "tri_state"))
      (node (ref "H04") (pin "K2") (pinfunction "1_K2") (pintype "bidirectional"))
    )
    (net (code "51") (name "MEM03") (class "Default")
      (node (ref "E12") (pin "12") (pinfunction "Y4_12") (pintype "tri_state"))
      (node (ref "H04") (pin "M2") (pinfunction "1_M2") (pintype "bidirectional"))
    )
    (net (code "52") (name "MEM04") (class "Default")
      (node (ref "E12") (pin "9") (pinfunction "Y1_9") (pintype "tri_state"))
      (node (ref "H04") (pin "P2") (pinfunction "1_P2") (pintype "bidirectional"))
    )
    (net (code "53") (name "MEM05") (class "Default")
      (node (ref "E12") (pin "7") (pinfunction "Y2_7") (pintype "tri_state"))
      (node (ref "H04") (pin "S2") (pinfunction "1_S2") (pintype "bidirectional"))
    )
    (net (code "54") (name "MEM06") (class "Default")
      (node (ref "E12") (pin "5") (pinfunction "Y3_5") (pintype "tri_state"))
      (node (ref "H04") (pin "T2") (pinfunction "1_T2") (pintype "bidirectional"))
    )
    (net (code "55") (name "MEM07") (class "Default")
      (node (ref "E12") (pin "3") (pinfunction "Y4_3") (pintype "tri_state"))
      (node (ref "H04") (pin "V2") (pinfunction "1_V2") (pintype "bidirectional"))
    )
    (net (code "56") (name "MEM08") (class "Default")
      (node (ref "E13") (pin "18") (pinfunction "Y1_18") (pintype "tri_state"))
      (node (ref "H05") (pin "D2") (pinfunction "1_D2") (pintype "bidirectional"))
      (node (ref "SV4") (pin "41") (pinfunction "41_41") (pintype "passive"))
      (node (ref "SV5") (pin "41") (pinfunction "41_41") (pintype "passive"))
    )
    (net (code "57") (name "MEM09") (class "Default")
      (node (ref "E13") (pin "16") (pinfunction "Y2_16") (pintype "tri_state"))
      (node (ref "H05") (pin "E2") (pinfunction "1_E2") (pintype "bidirectional"))
      (node (ref "SV4") (pin "39") (pinfunction "39_39") (pintype "passive"))
      (node (ref "SV5") (pin "39") (pinfunction "39_39") (pintype "passive"))
    )
    (net (code "58") (name "MEM10") (class "Default")
      (node (ref "E13") (pin "14") (pinfunction "Y3_14") (pintype "tri_state"))
      (node (ref "H05") (pin "H2") (pinfunction "1_H2") (pintype "bidirectional"))
      (node (ref "SV4") (pin "40") (pinfunction "40_40") (pintype "passive"))
      (node (ref "SV5") (pin "40") (pinfunction "40_40") (pintype "passive"))
    )
    (net (code "59") (name "MEM11") (class "Default")
      (node (ref "E13") (pin "12") (pinfunction "Y4_12") (pintype "tri_state"))
      (node (ref "H05") (pin "K2") (pinfunction "1_K2") (pintype "bidirectional"))
      (node (ref "SV4") (pin "37") (pinfunction "37_37") (pintype "passive"))
      (node (ref "SV5") (pin "37") (pinfunction "37_37") (pintype "passive"))
    )
    (net (code "60") (name "MEMDONE(0)") (class "Default")
      (node (ref "E4") (pin "11") (pinfunction "O_11") (pintype "open_collector"))
      (node (ref "H05") (pin "S2") (pinfunction "1_S2") (pintype "bidirectional"))
    )
    (net (code "61") (name "MEMDONE(1)") (class "Default")
      (node (ref "E2") (pin "5") (pinfunction "Q_5") (pintype "output"))
      (node (ref "E4") (pin "12") (pinfunction "I0_12") (pintype "input"))
      (node (ref "E4") (pin "13") (pinfunction "I1_13") (pintype "input"))
    )
    (net (code "62") (name "MEMSTART(0)") (class "Default")
      (node (ref "E3") (pin "1") (pinfunction "A_1") (pintype "input"))
      (node (ref "E3") (pin "9") (pinfunction "A_9") (pintype "input"))
      (node (ref "E5") (pin "6") (pinfunction "O_6") (pintype "output"))
    )
    (net (code "63") (name "MEMSTART(1)") (class "Default")
      (node (ref "E5") (pin "5") (pinfunction "I1_5") (pintype "input"))
      (node (ref "H05") (pin "M2") (pinfunction "1_M2") (pintype "bidirectional"))
      (node (ref "R1") (pin "1") (pinfunction "1_1") (pintype "passive"))
    )
    (net (code "64") (name "MEM_P") (class "Default")
      (node (ref "E13") (pin "9") (pinfunction "Y1_9") (pintype "tri_state"))
      (node (ref "H04") (pin "D2") (pinfunction "1_D2") (pintype "bidirectional"))
    )
    (net (code "65") (name "Net-(E1A-C)") (class "Default")
      (node (ref "C19") (pin "2") (pinfunction "2_2") (pintype "passive"))
      (node (ref "E1") (pin "14") (pinfunction "C_14") (pintype "input"))
    )
    (net (code "66") (name "Net-(E1A-R{slash}C)") (class "Default")
      (node (ref "C19") (pin "1") (pinfunction "1_1") (pintype "passive"))
      (node (ref "E1") (pin "15") (pinfunction "R/C_15") (pintype "input"))
      (node (ref "R6") (pin "2") (pinfunction "2_2") (pintype "passive"))
    )
    (net (code "67") (name "Net-(E1B-C)") (class "Default")
      (node (ref "C20") (pin "2") (pinfunction "2_2") (pintype "passive"))
      (node (ref "E1") (pin "6") (pinfunction "C_6") (pintype "input"))
    )
    (net (code "68") (name "Net-(E1B-R{slash}C)") (class "Default")
      (node (ref "C20") (pin "1") (pinfunction "1_1") (pintype "passive"))
      (node (ref "E1") (pin "7") (pinfunction "R/C_7") (pintype "input"))
      (node (ref "R7") (pin "2") (pinfunction "2_2") (pintype "passive"))
    )
    (net (code "69") (name "Net-(E2A-C)") (class "Default")
      (node (ref "C21") (pin "2") (pinfunction "2_2") (pintype "passive"))
      (node (ref "E2") (pin "14") (pinfunction "C_14") (pintype "input"))
    )
    (net (code "70") (name "Net-(E2A-R{slash}C)") (class "Default")
      (node (ref "C21") (pin "1") (pinfunction "1_1") (pintype "passive"))
      (node (ref "E2") (pin "15") (pinfunction "R/C_15") (pintype "input"))
      (node (ref "R8") (pin "2") (pinfunction "2_2") (pintype "passive"))
    )
    (net (code "71") (name "Net-(E2B-C)") (class "Default")
      (node (ref "C22") (pin "2") (pinfunction "2_2") (pintype "passive"))
      (node (ref "E2") (pin "6") (pinfunction "C_6") (pintype "input"))
    )
    (net (code "72") (name "Net-(E2B-R{slash}C)") (class "Default")
      (node (ref "C22") (pin "1") (pinfunction "1_1") (pintype "passive"))
      (node (ref "E2") (pin "7") (pinfunction "R/C_7") (pintype "input"))
      (node (ref "R9") (pin "2") (pinfunction "2_2") (pintype "passive"))
    )
    (net (code "73") (name "Net-(E3A-C)") (class "Default")
      (node (ref "C17") (pin "2") (pinfunction "2_2") (pintype "passive"))
      (node (ref "E3") (pin "14") (pinfunction "C_14") (pintype "input"))
    )
    (net (code "74") (name "Net-(E3A-R{slash}C)") (class "Default")
      (node (ref "C17") (pin "1") (pinfunction "1_1") (pintype "passive"))
      (node (ref "E3") (pin "15") (pinfunction "R/C_15") (pintype "input"))
      (node (ref "R4") (pin "2") (pinfunction "2_2") (pintype "passive"))
    )
    (net (code "75") (name "Net-(E3B-C)") (class "Default")
      (node (ref "C18") (pin "2") (pinfunction "2_2") (pintype "passive"))
      (node (ref "E3") (pin "6") (pinfunction "C_6") (pintype "input"))
    )
    (net (code "76") (name "Net-(E3B-R{slash}C)") (class "Default")
      (node (ref "C18") (pin "1") (pinfunction "1_1") (pintype "passive"))
      (node (ref "E3") (pin "7") (pinfunction "R/C_7") (pintype "input"))
      (node (ref "R5") (pin "2") (pinfunction "2_2") (pintype "passive"))
    )
    (net (code "77") (name "Net-(E16-I{slash}O5)") (class "Default")
      (node (ref "E16") (pin "17") (pinfunction "I/O5_17") (pintype "bidirectional"))
      (node (ref "E16A") (pin "17") (pinfunction "I/O5_17") (pintype "bidirectional"))
    )
    (net (code "78") (name "Net-(E16-I{slash}O6)") (class "Default")
      (node (ref "E16") (pin "18") (pinfunction "I/O6_18") (pintype "bidirectional"))
      (node (ref "E16A") (pin "18") (pinfunction "I/O6_18") (pintype "bidirectional"))
    )
    (net (code "79") (name "Net-(E16-I{slash}O7)") (class "Default")
      (node (ref "E16") (pin "19") (pinfunction "I/O7_19") (pintype "bidirectional"))
      (node (ref "E16A") (pin "19") (pinfunction "I/O7_19") (pintype "bidirectional"))
    )
    (net (code "80") (name "Net-(E18A-I0)") (class "Default")
      (node (ref "E18") (pin "1") (pinfunction "I0_1") (pintype "input"))
      (node (ref "FIELDS") (pin "2") (pinfunction "2_2") (pintype "passive"))
    )
    (net (code "81") (name "Net-(E18A-I1)") (class "Default")
      (node (ref "E18") (pin "2") (pinfunction "I1_2") (pintype "input"))
      (node (ref "FIELDS") (pin "4") (pinfunction "4_4") (pintype "passive"))
    )
    (net (code "82") (name "Net-(E18A-I2)") (class "Default")
      (node (ref "E18") (pin "3") (pinfunction "I2_3") (pintype "input"))
      (node (ref "FIELDS") (pin "6") (pinfunction "6_6") (pintype "passive"))
    )
    (net (code "83") (name "Net-(E18A-I3)") (class "Default")
      (node (ref "E18") (pin "4") (pinfunction "I3_4") (pintype "input"))
      (node (ref "FIELDS") (pin "8") (pinfunction "8_8") (pintype "passive"))
    )
    (net (code "84") (name "Net-(E18A-I4)") (class "Default")
      (node (ref "E18") (pin "5") (pinfunction "I4_5") (pintype "input"))
      (node (ref "FIELDS") (pin "10") (pinfunction "10_10") (pintype "passive"))
    )
    (net (code "85") (name "Net-(E18A-I5)") (class "Default")
      (node (ref "E18") (pin "6") (pinfunction "I5_6") (pintype "input"))
      (node (ref "FIELDS") (pin "12") (pinfunction "12_12") (pintype "passive"))
    )
    (net (code "86") (name "Net-(E18A-I6)") (class "Default")
      (node (ref "E18") (pin "11") (pinfunction "I6_11") (pintype "input"))
      (node (ref "FIELDS") (pin "16") (pinfunction "16_16") (pintype "passive"))
    )
    (net (code "87") (name "Net-(E18A-I7)") (class "Default")
      (node (ref "E18") (pin "12") (pinfunction "I7_12") (pintype "input"))
      (node (ref "FIELDS") (pin "14") (pinfunction "14_14") (pintype "passive"))
    )
    (net (code "88") (name "Net-(E19A-Y0)") (class "Default")
      (node (ref "E19") (pin "15") (pinfunction "Y0_15") (pintype "output"))
      (node (ref "FIELDS") (pin "1") (pinfunction "1_1") (pintype "passive"))
    )
    (net (code "89") (name "Net-(E19A-Y1)") (class "Default")
      (node (ref "E19") (pin "14") (pinfunction "Y1_14") (pintype "output"))
      (node (ref "FIELDS") (pin "3") (pinfunction "3_3") (pintype "passive"))
    )
    (net (code "90") (name "Net-(E19A-Y2)") (class "Default")
      (node (ref "E19") (pin "13") (pinfunction "Y2_13") (pintype "output"))
      (node (ref "FIELDS") (pin "5") (pinfunction "5_5") (pintype "passive"))
    )
    (net (code "91") (name "Net-(E19A-Y3)") (class "Default")
      (node (ref "E19") (pin "12") (pinfunction "Y3_12") (pintype "output"))
      (node (ref "FIELDS") (pin "7") (pinfunction "7_7") (pintype "passive"))
    )
    (net (code "92") (name "Net-(E19A-Y4)") (class "Default")
      (node (ref "E19") (pin "11") (pinfunction "Y4_11") (pintype "output"))
      (node (ref "FIELDS") (pin "9") (pinfunction "9_9") (pintype "passive"))
    )
    (net (code "93") (name "Net-(E19A-Y5)") (class "Default")
      (node (ref "E19") (pin "10") (pinfunction "Y5_10") (pintype "output"))
      (node (ref "FIELDS") (pin "11") (pinfunction "11_11") (pintype "passive"))
    )
    (net (code "94") (name "Net-(E19A-Y6)") (class "Default")
      (node (ref "E19") (pin "9") (pinfunction "Y6_9") (pintype "output"))
      (node (ref "FIELDS") (pin "13") (pinfunction "13_13") (pintype "passive"))
    )
    (net (code "95") (name "Net-(E19A-Y7)") (class "Default")
      (node (ref "E19") (pin "7") (pinfunction "Y7_7") (pintype "output"))
      (node (ref "FIELDS") (pin "15") (pinfunction "15_15") (pintype "passive"))
    )
    (net (code "96") (name "OE(0)") (class "Default")
      (node (ref "E12") (pin "1") (pinfunction "G_1") (pintype "input"))
      (node (ref "E12") (pin "19") (pinfunction "G_19") (pintype "input"))
      (node (ref "E13") (pin "1") (pinfunction "G_1") (pintype "input"))
      (node (ref "E13") (pin "19") (pinfunction "G_19") (pintype "input"))
      (node (ref "E16") (pin "22") (pinfunction "~{OE}_22") (pintype "input"))
      (node (ref "E16A") (pin "22") (pinfunction "~{OE}_22") (pintype "input"))
      (node (ref "E17") (pin "22") (pinfunction "~{OE}_22") (pintype "input"))
      (node (ref "E17A") (pin "22") (pinfunction "~{OE}_22") (pintype "input"))
      (node (ref "E3") (pin "4") (pinfunction "~{Q}_4") (pintype "output"))
      (node (ref "E5") (pin "10") (pinfunction "I1_10") (pintype "input"))
      (node (ref "SV2") (pin "22") (pinfunction "22_22") (pintype "passive"))
      (node (ref "SV4") (pin "22") (pinfunction "22_22") (pintype "passive"))
      (node (ref "SV5") (pin "22") (pinfunction "22_22") (pintype "passive"))
    )
    (net (code "97") (name "PARITY") (class "Default")
      (node (ref "E13") (pin "11") (pinfunction "A1_11") (pintype "input"))
      (node (ref "E13") (pin "13") (pinfunction "A2_13") (pintype "input"))
      (node (ref "E13") (pin "15") (pinfunction "A3_15") (pintype "input"))
      (node (ref "E13") (pin "17") (pinfunction "A4_17") (pintype "input"))
      (node (ref "E15") (pin "9") (pinfunction "Y1_9") (pintype "tri_state"))
      (node (ref "E16") (pin "16") (pinfunction "I/O4_16") (pintype "bidirectional"))
      (node (ref "E16A") (pin "16") (pinfunction "I/O4_16") (pintype "bidirectional"))
      (node (ref "SV2") (pin "3") (pinfunction "3_3") (pintype "passive"))
      (node (ref "SV3") (pin "3") (pinfunction "3_3") (pintype "passive"))
      (node (ref "SV4") (pin "3") (pinfunction "3_3") (pintype "passive"))
    )
    (net (code "98") (name "SDELAY") (class "Default")
      (node (ref "E2") (pin "1") (pinfunction "A_1") (pintype "input"))
      (node (ref "E3") (pin "5") (pinfunction "Q_5") (pintype "output"))
    )
    (net (code "99") (name "STROBE(0)") (class "Default")
      (node (ref "E4") (pin "8") (pinfunction "O_8") (pintype "open_collector"))
      (node (ref "H05") (pin "P2") (pinfunction "1_P2") (pintype "bidirectional"))
    )
    (net (code "100") (name "STROBE(1)") (class "Default")
      (node (ref "E2") (pin "13") (pinfunction "Q_13") (pintype "output"))
      (node (ref "E4") (pin "10") (pinfunction "I1_10") (pintype "input"))
      (node (ref "E4") (pin "9") (pinfunction "I0_9") (pintype "input"))
    )
    (net (code "101") (name "VCC") (class "Default")
      (node (ref "C10") (pin "1") (pinfunction "1_1") (pintype "passive"))
      (node (ref "C11") (pin "1") (pinfunction "1_1") (pintype "passive"))
      (node (ref "C12") (pin "1") (pinfunction "1_1") (pintype "passive"))
      (node (ref "C13") (pin "1") (pinfunction "1_1") (pintype "passive"))
      (node (ref "C14") (pin "1") (pinfunction "1_1") (pintype "passive"))
      (node (ref "C15") (pin "1") (pinfunction "1_1") (pintype "passive"))
      (node (ref "C16") (pin "1") (pinfunction "1_1") (pintype "passive"))
      (node (ref "C2") (pin "1") (pinfunction "1_1") (pintype "passive"))
      (node (ref "C3") (pin "1") (pinfunction "1_1") (pintype "passive"))
      (node (ref "C4") (pin "1") (pinfunction "1_1") (pintype "passive"))
      (node (ref "C5") (pin "1") (pinfunction "1_1") (pintype "passive"))
      (node (ref "C6") (pin "1") (pinfunction "1_1") (pintype "passive"))
      (node (ref "C9") (pin "1") (pinfunction "1_1") (pintype "passive"))
      (node (ref "E1") (pin "10") (pinfunction "B_10") (pintype "input"))
      (node (ref "E1") (pin "11") (pinfunction "CLR_11") (pintype "input"))
      (node (ref "E1") (pin "2") (pinfunction "B_2") (pintype "input"))
      (node (ref "E1") (pin "3") (pinfunction "CLR_3") (pintype "input"))
      (node (ref "E16") (pin "28") (pinfunction "VCC_28") (pintype "power_in"))
      (node (ref "E16A") (pin "28") (pinfunction "VCC_28") (pintype "power_in"))
      (node (ref "E17") (pin "28") (pinfunction "VCC_28") (pintype "power_in"))
      (node (ref "E17A") (pin "28") (pinfunction "VCC_28") (pintype "power_in"))
      (node (ref "E19") (pin "6") (pinfunction "G1_6") (pintype "input"))
      (node (ref "E2") (pin "10") (pinfunction "B_10") (pintype "input"))
      (node (ref "E2") (pin "11") (pinfunction "CLR_11") (pintype "input"))
      (node (ref "E2") (pin "2") (pinfunction "B_2") (pintype "input"))
      (node (ref "E2") (pin "3") (pinfunction "CLR_3") (pintype "input"))
      (node (ref "E3") (pin "10") (pinfunction "B_10") (pintype "input"))
      (node (ref "E3") (pin "11") (pinfunction "CLR_11") (pintype "input"))
      (node (ref "E3") (pin "2") (pinfunction "B_2") (pintype "input"))
      (node (ref "E3") (pin "3") (pinfunction "CLR_3") (pintype "input"))
      (node (ref "E4") (pin "1") (pinfunction "I0_1") (pintype "input"))
      (node (ref "E4") (pin "2") (pinfunction "I1_2") (pintype "input"))
      (node (ref "E4") (pin "4") (pinfunction "I0_4") (pintype "input"))
      (node (ref "E4") (pin "5") (pinfunction "I1_5") (pintype "input"))
      (node (ref "R4") (pin "1") (pinfunction "1_1") (pintype "passive"))
      (node (ref "R5") (pin "1") (pinfunction "1_1") (pintype "passive"))
      (node (ref "R6") (pin "1") (pinfunction "1_1") (pintype "passive"))
      (node (ref "R7") (pin "1") (pinfunction "1_1") (pintype "passive"))
      (node (ref "R8") (pin "1") (pinfunction "1_1") (pintype "passive"))
      (node (ref "R9") (pin "1") (pinfunction "1_1") (pintype "passive"))
      (node (ref "SV1") (pin "49") (pinfunction "49_49") (pintype "passive"))
      (node (ref "SV1") (pin "50") (pinfunction "50_50") (pintype "passive"))
      (node (ref "SV2") (pin "49") (pinfunction "49_49") (pintype "passive"))
      (node (ref "SV2") (pin "50") (pinfunction "50_50") (pintype "passive"))
      (node (ref "SV3") (pin "49") (pinfunction "49_49") (pintype "passive"))
      (node (ref "SV3") (pin "50") (pinfunction "50_50") (pintype "passive"))
      (node (ref "SV4") (pin "49") (pinfunction "49_49") (pintype "passive"))
      (node (ref "SV4") (pin "50") (pinfunction "50_50") (pintype "passive"))
      (node (ref "SV5") (pin "49") (pinfunction "49_49") (pintype "passive"))
      (node (ref "SV5") (pin "50") (pinfunction "50_50") (pintype "passive"))
      (node (ref "X1") (pin "1") (pinfunction "KL_1") (pintype "passive"))
    )
    (net (code "102") (name "WE(0)") (class "Default")
      (node (ref "E1") (pin "4") (pinfunction "~{Q}_4") (pintype "output"))
      (node (ref "E14") (pin "1") (pinfunction "G_1") (pintype "input"))
      (node (ref "E14") (pin "19") (pinfunction "G_19") (pintype "input"))
      (node (ref "E15") (pin "1") (pinfunction "G_1") (pintype "input"))
      (node (ref "E15") (pin "19") (pinfunction "G_19") (pintype "input"))
      (node (ref "E16") (pin "27") (pinfunction "~{WE}_27") (pintype "input"))
      (node (ref "E16A") (pin "27") (pinfunction "~{WE}_27") (pintype "input"))
      (node (ref "E17") (pin "27") (pinfunction "~{WE}_27") (pintype "input"))
      (node (ref "E17A") (pin "27") (pinfunction "~{WE}_27") (pintype "input"))
      (node (ref "E5") (pin "9") (pinfunction "I0_9") (pintype "input"))
      (node (ref "SV2") (pin "32") (pinfunction "32_32") (pintype "passive"))
      (node (ref "SV3") (pin "32") (pinfunction "32_32") (pintype "passive"))
      (node (ref "SV5") (pin "32") (pinfunction "32_32") (pintype "passive"))
    )
    (net (code "103") (name "unconnected-(E1A-Q-Pad13)") (class "Default")
      (node (ref "E1") (pin "13") (pinfunction "Q_13") (pintype "output"))
    )
    (net (code "104") (name "unconnected-(E1B-~{Q}-Pad12)") (class "Default")
      (node (ref "E1") (pin "12") (pinfunction "~{Q}_12") (pintype "output"))
    )
    (net (code "105") (name "unconnected-(E2A-~{Q}-Pad4)") (class "Default")
      (node (ref "E2") (pin "4") (pinfunction "~{Q}_4") (pintype "output"))
    )
    (net (code "106") (name "unconnected-(E2B-~{Q}-Pad12)") (class "Default")
      (node (ref "E2") (pin "12") (pinfunction "~{Q}_12") (pintype "output"))
    )
    (net (code "107") (name "unconnected-(E3A-Q-Pad13)") (class "Default")
      (node (ref "E3") (pin "13") (pinfunction "Q_13") (pintype "output"))
    )
    (net (code "108") (name "unconnected-(E3B-~{Q}-Pad12)") (class "Default")
      (node (ref "E3") (pin "12") (pinfunction "~{Q}_12") (pintype "output"))
    )
    (net (code "109") (name "unconnected-(E4A-O-Pad3)") (class "Default")
      (node (ref "E4") (pin "3") (pinfunction "O_3") (pintype "open_collector"))
    )
    (net (code "110") (name "unconnected-(E4B-O-Pad6)") (class "Default")
      (node (ref "E4") (pin "6") (pinfunction "O_6") (pintype "open_collector"))
    )
    (net (code "111") (name "unconnected-(E13B-Y2-Pad7)") (class "Default")
      (node (ref "E13") (pin "7") (pinfunction "Y2_7") (pintype "tri_state"))
    )
    (net (code "112") (name "unconnected-(E13B-Y3-Pad5)") (class "Default")
      (node (ref "E13") (pin "5") (pinfunction "Y3_5") (pintype "tri_state"))
    )
    (net (code "113") (name "unconnected-(E13B-Y4-Pad3)") (class "Default")
      (node (ref "E13") (pin "3") (pinfunction "Y4_3") (pintype "tri_state"))
    )
    (net (code "114") (name "unconnected-(E15B-Y2-Pad7)") (class "Default")
      (node (ref "E15") (pin "7") (pinfunction "Y2_7") (pintype "tri_state"))
    )
    (net (code "115") (name "unconnected-(E15B-Y3-Pad5)") (class "Default")
      (node (ref "E15") (pin "5") (pinfunction "Y3_5") (pintype "tri_state"))
    )
    (net (code "116") (name "unconnected-(E15B-Y4-Pad3)") (class "Default")
      (node (ref "E15") (pin "3") (pinfunction "Y4_3") (pintype "tri_state"))
    )
    (net (code "117") (name "unconnected-(SV1-Pad3)") (class "Default")
      (node (ref "SV1") (pin "3") (pinfunction "3_3") (pintype "passive"))
    )
    (net (code "118") (name "unconnected-(SV1-Pad4)") (class "Default")
      (node (ref "SV1") (pin "4") (pinfunction "4_4") (pintype "passive"))
    )
    (net (code "119") (name "unconnected-(SV1-Pad5)") (class "Default")
      (node (ref "SV1") (pin "5") (pinfunction "5_5") (pintype "passive"))
    )
    (net (code "120") (name "unconnected-(SV1-Pad6)") (class "Default")
      (node (ref "SV1") (pin "6") (pinfunction "6_6") (pintype "passive"))
    )
    (net (code "121") (name "unconnected-(SV1-Pad7)") (class "Default")
      (node (ref "SV1") (pin "7") (pinfunction "7_7") (pintype "passive"))
    )
    (net (code "122") (name "unconnected-(SV1-Pad8)") (class "Default")
      (node (ref "SV1") (pin "8") (pinfunction "8_8") (pintype "passive"))
    )
    (net (code "123") (name "unconnected-(SV1-Pad9)") (class "Default")
      (node (ref "SV1") (pin "9") (pinfunction "9_9") (pintype "passive"))
    )
    (net (code "124") (name "unconnected-(SV1-Pad10)") (class "Default")
      (node (ref "SV1") (pin "10") (pinfunction "10_10") (pintype "passive"))
    )
    (net (code "125") (name "unconnected-(SV1-Pad11)") (class "Default")
      (node (ref "SV1") (pin "11") (pinfunction "11_11") (pintype "passive"))
    )
    (net (code "126") (name "unconnected-(SV1-Pad12)") (class "Default")
      (node (ref "SV1") (pin "12") (pinfunction "12_12") (pintype "passive"))
    )
    (net (code "127") (name "unconnected-(SV1-Pad13)") (class "Default")
      (node (ref "SV1") (pin "13") (pinfunction "13_13") (pintype "passive"))
    )
    (net (code "128") (name "unconnected-(SV1-Pad14)") (class "Default")
      (node (ref "SV1") (pin "14") (pinfunction "14_14") (pintype "passive"))
    )
    (net (code "129") (name "unconnected-(SV1-Pad15)") (class "Default")
      (node (ref "SV1") (pin "15") (pinfunction "15_15") (pintype "passive"))
    )
    (net (code "130") (name "unconnected-(SV1-Pad16)") (class "Default")
      (node (ref "SV1") (pin "16") (pinfunction "16_16") (pintype "passive"))
    )
    (net (code "131") (name "unconnected-(SV1-Pad17)") (class "Default")
      (node (ref "SV1") (pin "17") (pinfunction "17_17") (pintype "passive"))
    )
    (net (code "132") (name "unconnected-(SV1-Pad18)") (class "Default")
      (node (ref "SV1") (pin "18") (pinfunction "18_18") (pintype "passive"))
    )
    (net (code "133") (name "unconnected-(SV1-Pad19)") (class "Default")
      (node (ref "SV1") (pin "19") (pinfunction "19_19") (pintype "passive"))
    )
    (net (code "134") (name "unconnected-(SV1-Pad21)") (class "Default")
      (node (ref "SV1") (pin "21") (pinfunction "21_21") (pintype "passive"))
    )
    (net (code "135") (name "unconnected-(SV1-Pad22)") (class "Default")
      (node (ref "SV1") (pin "22") (pinfunction "22_22") (pintype "passive"))
    )
    (net (code "136") (name "unconnected-(SV1-Pad23)") (class "Default")
      (node (ref "SV1") (pin "23") (pinfunction "23_23") (pintype "passive"))
    )
    (net (code "137") (name "unconnected-(SV1-Pad25)") (class "Default")
      (node (ref "SV1") (pin "25") (pinfunction "25_25") (pintype "passive"))
    )
    (net (code "138") (name "unconnected-(SV1-Pad32)") (class "Default")
      (node (ref "SV1") (pin "32") (pinfunction "32_32") (pintype "passive"))
    )
    (net (code "139") (name "unconnected-(SV1-Pad35)") (class "Default")
      (node (ref "SV1") (pin "35") (pinfunction "35_35") (pintype "passive"))
    )
    (net (code "140") (name "unconnected-(SV1-Pad36)") (class "Default")
      (node (ref "SV1") (pin "36") (pinfunction "36_36") (pintype "passive"))
    )
    (net (code "141") (name "unconnected-(SV1-Pad37)") (class "Default")
      (node (ref "SV1") (pin "37") (pinfunction "37_37") (pintype "passive"))
    )
    (net (code "142") (name "unconnected-(SV1-Pad38)") (class "Default")
      (node (ref "SV1") (pin "38") (pinfunction "38_38") (pintype "passive"))
    )
    (net (code "143") (name "unconnected-(SV1-Pad39)") (class "Default")
      (node (ref "SV1") (pin "39") (pinfunction "39_39") (pintype "passive"))
    )
    (net (code "144") (name "unconnected-(SV1-Pad40)") (class "Default")
      (node (ref "SV1") (pin "40") (pinfunction "40_40") (pintype "passive"))
    )
    (net (code "145") (name "unconnected-(SV1-Pad41)") (class "Default")
      (node (ref "SV1") (pin "41") (pinfunction "41_41") (pintype "passive"))
    )
    (net (code "146") (name "unconnected-(SV1-Pad42)") (class "Default")
      (node (ref "SV1") (pin "42") (pinfunction "42_42") (pintype "passive"))
    )
    (net (code "147") (name "unconnected-(SV1-Pad45)") (class "Default")
      (node (ref "SV1") (pin "45") (pinfunction "45_45") (pintype "passive"))
    )
    (net (code "148") (name "unconnected-(SV1-Pad47)") (class "Default")
      (node (ref "SV1") (pin "47") (pinfunction "47_47") (pintype "passive"))
    )
    (net (code "149") (name "unconnected-(SV1-Pad48)") (class "Default")
      (node (ref "SV1") (pin "48") (pinfunction "48_48") (pintype "passive"))
    )
    (net (code "150") (name "unconnected-(SV2-Pad34)") (class "Default")
      (node (ref "SV2") (pin "34") (pinfunction "34_34") (pintype "passive"))
    )
    (net (code "151") (name "unconnected-(SV2-Pad37)") (class "Default")
      (node (ref "SV2") (pin "37") (pinfunction "37_37") (pintype "passive"))
    )
    (net (code "152") (name "unconnected-(SV2-Pad39)") (class "Default")
      (node (ref "SV2") (pin "39") (pinfunction "39_39") (pintype "passive"))
    )
    (net (code "153") (name "unconnected-(SV2-Pad40)") (class "Default")
      (node (ref "SV2") (pin "40") (pinfunction "40_40") (pintype "passive"))
    )
    (net (code "154") (name "unconnected-(SV2-Pad41)") (class "Default")
      (node (ref "SV2") (pin "41") (pinfunction "41_41") (pintype "passive"))
    )
    (net (code "155") (name "unconnected-(SV2-Pad42)") (class "Default")
      (node (ref "SV2") (pin "42") (pinfunction "42_42") (pintype "passive"))
    )
    (net (code "156") (name "unconnected-(SV2-Pad43)") (class "Default")
      (node (ref "SV2") (pin "43") (pinfunction "43_43") (pintype "passive"))
    )
    (net (code "157") (name "unconnected-(SV2-Pad44)") (class "Default")
      (node (ref "SV2") (pin "44") (pinfunction "44_44") (pintype "passive"))
    )
    (net (code "158") (name "unconnected-(SV2-Pad45)") (class "Default")
      (node (ref "SV2") (pin "45") (pinfunction "45_45") (pintype "passive"))
    )
    (net (code "159") (name "unconnected-(SV2-Pad46)") (class "Default")
      (node (ref "SV2") (pin "46") (pinfunction "46_46") (pintype "passive"))
    )
    (net (code "160") (name "unconnected-(SV2-Pad47)") (class "Default")
      (node (ref "SV2") (pin "47") (pinfunction "47_47") (pintype "passive"))
    )
    (net (code "161") (name "unconnected-(SV2-Pad48)") (class "Default")
      (node (ref "SV2") (pin "48") (pinfunction "48_48") (pintype "passive"))
    )
    (net (code "162") (name "unconnected-(SV3-Pad15)") (class "Default")
      (node (ref "SV3") (pin "15") (pinfunction "15_15") (pintype "passive"))
    )
    (net (code "163") (name "unconnected-(SV3-Pad17)") (class "Default")
      (node (ref "SV3") (pin "17") (pinfunction "17_17") (pintype "passive"))
    )
    (net (code "164") (name "unconnected-(SV3-Pad18)") (class "Default")
      (node (ref "SV3") (pin "18") (pinfunction "18_18") (pintype "passive"))
    )
    (net (code "165") (name "unconnected-(SV3-Pad19)") (class "Default")
      (node (ref "SV3") (pin "19") (pinfunction "19_19") (pintype "passive"))
    )
    (net (code "166") (name "unconnected-(SV3-Pad20)") (class "Default")
      (node (ref "SV3") (pin "20") (pinfunction "20_20") (pintype "passive"))
    )
    (net (code "167") (name "unconnected-(SV3-Pad21)") (class "Default")
      (node (ref "SV3") (pin "21") (pinfunction "21_21") (pintype "passive"))
    )
    (net (code "168") (name "unconnected-(SV3-Pad22)") (class "Default")
      (node (ref "SV3") (pin "22") (pinfunction "22_22") (pintype "passive"))
    )
    (net (code "169") (name "unconnected-(SV3-Pad23)") (class "Default")
      (node (ref "SV3") (pin "23") (pinfunction "23_23") (pintype "passive"))
    )
    (net (code "170") (name "unconnected-(SV3-Pad24)") (class "Default")
      (node (ref "SV3") (pin "24") (pinfunction "24_24") (pintype "passive"))
    )
    (net (code "171") (name "unconnected-(SV3-Pad25)") (class "Default")
      (node (ref "SV3") (pin "25") (pinfunction "25_25") (pintype "passive"))
    )
    (net (code "172") (name "unconnected-(SV3-Pad26)") (class "Default")
      (node (ref "SV3") (pin "26") (pinfunction "26_26") (pintype "passive"))
    )
    (net (code "173") (name "unconnected-(SV3-Pad27)") (class "Default")
      (node (ref "SV3") (pin "27") (pinfunction "27_27") (pintype "passive"))
    )
    (net (code "174") (name "unconnected-(SV3-Pad28)") (class "Default")
      (node (ref "SV3") (pin "28") (pinfunction "28_28") (pintype "passive"))
    )
    (net (code "175") (name "unconnected-(SV3-Pad29)") (class "Default")
      (node (ref "SV3") (pin "29") (pinfunction "29_29") (pintype "passive"))
    )
    (net (code "176") (name "unconnected-(SV3-Pad34)") (class "Default")
      (node (ref "SV3") (pin "34") (pinfunction "34_34") (pintype "passive"))
    )
    (net (code "177") (name "unconnected-(SV3-Pad37)") (class "Default")
      (node (ref "SV3") (pin "37") (pinfunction "37_37") (pintype "passive"))
    )
    (net (code "178") (name "unconnected-(SV3-Pad39)") (class "Default")
      (node (ref "SV3") (pin "39") (pinfunction "39_39") (pintype "passive"))
    )
    (net (code "179") (name "unconnected-(SV3-Pad40)") (class "Default")
      (node (ref "SV3") (pin "40") (pinfunction "40_40") (pintype "passive"))
    )
    (net (code "180") (name "unconnected-(SV3-Pad41)") (class "Default")
      (node (ref "SV3") (pin "41") (pinfunction "41_41") (pintype "passive"))
    )
    (net (code "181") (name "unconnected-(SV3-Pad45)") (class "Default")
      (node (ref "SV3") (pin "45") (pinfunction "45_45") (pintype "passive"))
    )
    (net (code "182") (name "unconnected-(SV3-Pad47)") (class "Default")
      (node (ref "SV3") (pin "47") (pinfunction "47_47") (pintype "passive"))
    )
    (net (code "183") (name "unconnected-(SV3-Pad48)") (class "Default")
      (node (ref "SV3") (pin "48") (pinfunction "48_48") (pintype "passive"))
    )
    (net (code "184") (name "unconnected-(SV4-Pad15)") (class "Default")
      (node (ref "SV4") (pin "15") (pinfunction "15_15") (pintype "passive"))
    )
    (net (code "185") (name "unconnected-(SV4-Pad17)") (class "Default")
      (node (ref "SV4") (pin "17") (pinfunction "17_17") (pintype "passive"))
    )
    (net (code "186") (name "unconnected-(SV4-Pad18)") (class "Default")
      (node (ref "SV4") (pin "18") (pinfunction "18_18") (pintype "passive"))
    )
    (net (code "187") (name "unconnected-(SV4-Pad19)") (class "Default")
      (node (ref "SV4") (pin "19") (pinfunction "19_19") (pintype "passive"))
    )
    (net (code "188") (name "unconnected-(SV4-Pad20)") (class "Default")
      (node (ref "SV4") (pin "20") (pinfunction "20_20") (pintype "passive"))
    )
    (net (code "189") (name "unconnected-(SV4-Pad21)") (class "Default")
      (node (ref "SV4") (pin "21") (pinfunction "21_21") (pintype "passive"))
    )
    (net (code "190") (name "unconnected-(SV4-Pad23)") (class "Default")
      (node (ref "SV4") (pin "23") (pinfunction "23_23") (pintype "passive"))
    )
    (net (code "191") (name "unconnected-(SV4-Pad24)") (class "Default")
      (node (ref "SV4") (pin "24") (pinfunction "24_24") (pintype "passive"))
    )
    (net (code "192") (name "unconnected-(SV4-Pad25)") (class "Default")
      (node (ref "SV4") (pin "25") (pinfunction "25_25") (pintype "passive"))
    )
    (net (code "193") (name "unconnected-(SV4-Pad26)") (class "Default")
      (node (ref "SV4") (pin "26") (pinfunction "26_26") (pintype "passive"))
    )
    (net (code "194") (name "unconnected-(SV4-Pad27)") (class "Default")
      (node (ref "SV4") (pin "27") (pinfunction "27_27") (pintype "passive"))
    )
    (net (code "195") (name "unconnected-(SV4-Pad28)") (class "Default")
      (node (ref "SV4") (pin "28") (pinfunction "28_28") (pintype "passive"))
    )
    (net (code "196") (name "unconnected-(SV4-Pad29)") (class "Default")
      (node (ref "SV4") (pin "29") (pinfunction "29_29") (pintype "passive"))
    )
    (net (code "197") (name "unconnected-(SV4-Pad30)") (class "Default")
      (node (ref "SV4") (pin "30") (pinfunction "30_30") (pintype "passive"))
    )
    (net (code "198") (name "unconnected-(SV4-Pad31)") (class "Default")
      (node (ref "SV4") (pin "31") (pinfunction "31_31") (pintype "passive"))
    )
    (net (code "199") (name "unconnected-(SV4-Pad32)") (class "Default")
      (node (ref "SV4") (pin "32") (pinfunction "32_32") (pintype "passive"))
    )
    (net (code "200") (name "unconnected-(SV4-Pad33)") (class "Default")
      (node (ref "SV4") (pin "33") (pinfunction "33_33") (pintype "passive"))
    )
    (net (code "201") (name "unconnected-(SV4-Pad34)") (class "Default")
      (node (ref "SV4") (pin "34") (pinfunction "34_34") (pintype "passive"))
    )
    (net (code "202") (name "unconnected-(SV4-Pad35)") (class "Default")
      (node (ref "SV4") (pin "35") (pinfunction "35_35") (pintype "passive"))
    )
    (net (code "203") (name "unconnected-(SV4-Pad36)") (class "Default")
      (node (ref "SV4") (pin "36") (pinfunction "36_36") (pintype "passive"))
    )
    (net (code "204") (name "unconnected-(SV4-Pad38)") (class "Default")
      (node (ref "SV4") (pin "38") (pinfunction "38_38") (pintype "passive"))
    )
    (net (code "205") (name "unconnected-(SV4-Pad42)") (class "Default")
      (node (ref "SV4") (pin "42") (pinfunction "42_42") (pintype "passive"))
    )
    (net (code "206") (name "unconnected-(SV4-Pad43)") (class "Default")
      (node (ref "SV4") (pin "43") (pinfunction "43_43") (pintype "passive"))
    )
    (net (code "207") (name "unconnected-(SV4-Pad44)") (class "Default")
      (node (ref "SV4") (pin "44") (pinfunction "44_44") (pintype "passive"))
    )
    (net (code "208") (name "unconnected-(SV4-Pad45)") (class "Default")
      (node (ref "SV4") (pin "45") (pinfunction "45_45") (pintype "passive"))
    )
    (net (code "209") (name "unconnected-(SV4-Pad46)") (class "Default")
      (node (ref "SV4") (pin "46") (pinfunction "46_46") (pintype "passive"))
    )
    (net (code "210") (name "unconnected-(SV4-Pad47)") (class "Default")
      (node (ref "SV4") (pin "47") (pinfunction "47_47") (pintype "passive"))
    )
    (net (code "211") (name "unconnected-(SV4-Pad48)") (class "Default")
      (node (ref "SV4") (pin "48") (pinfunction "48_48") (pintype "passive"))
    )
    (net (code "212") (name "unconnected-(SV5-Pad3)") (class "Default")
      (node (ref "SV5") (pin "3") (pinfunction "3_3") (pintype "passive"))
    )
    (net (code "213") (name "unconnected-(SV5-Pad4)") (class "Default")
      (node (ref "SV5") (pin "4") (pinfunction "4_4") (pintype "passive"))
    )
    (net (code "214") (name "unconnected-(SV5-Pad5)") (class "Default")
      (node (ref "SV5") (pin "5") (pinfunction "5_5") (pintype "passive"))
    )
    (net (code "215") (name "unconnected-(SV5-Pad6)") (class "Default")
      (node (ref "SV5") (pin "6") (pinfunction "6_6") (pintype "passive"))
    )
    (net (code "216") (name "unconnected-(SV5-Pad7)") (class "Default")
      (node (ref "SV5") (pin "7") (pinfunction "7_7") (pintype "passive"))
    )
    (net (code "217") (name "unconnected-(SV5-Pad8)") (class "Default")
      (node (ref "SV5") (pin "8") (pinfunction "8_8") (pintype "passive"))
    )
    (net (code "218") (name "unconnected-(SV5-Pad9)") (class "Default")
      (node (ref "SV5") (pin "9") (pinfunction "9_9") (pintype "passive"))
    )
    (net (code "219") (name "unconnected-(SV5-Pad10)") (class "Default")
      (node (ref "SV5") (pin "10") (pinfunction "10_10") (pintype "passive"))
    )
    (net (code "220") (name "unconnected-(SV5-Pad11)") (class "Default")
      (node (ref "SV5") (pin "11") (pinfunction "11_11") (pintype "passive"))
    )
    (net (code "221") (name "unconnected-(SV5-Pad12)") (class "Default")
      (node (ref "SV5") (pin "12") (pinfunction "12_12") (pintype "passive"))
    )
    (net (code "222") (name "unconnected-(SV5-Pad13)") (class "Default")
      (node (ref "SV5") (pin "13") (pinfunction "13_13") (pintype "passive"))
    )
    (net (code "223") (name "unconnected-(SV5-Pad14)") (class "Default")
      (node (ref "SV5") (pin "14") (pinfunction "14_14") (pintype "passive"))
    )
    (net (code "224") (name "unconnected-(SV5-Pad15)") (class "Default")
      (node (ref "SV5") (pin "15") (pinfunction "15_15") (pintype "passive"))
    )
    (net (code "225") (name "unconnected-(SV5-Pad16)") (class "Default")
      (node (ref "SV5") (pin "16") (pinfunction "16_16") (pintype "passive"))
    )
    (net (code "226") (name "unconnected-(SV5-Pad17)") (class "Default")
      (node (ref "SV5") (pin "17") (pinfunction "17_17") (pintype "passive"))
    )
    (net (code "227") (name "unconnected-(SV5-Pad19)") (class "Default")
      (node (ref "SV5") (pin "19") (pinfunction "19_19") (pintype "passive"))
    )
    (net (code "228") (name "unconnected-(SV5-Pad20)") (class "Default")
      (node (ref "SV5") (pin "20") (pinfunction "20_20") (pintype "passive"))
    )
    (net (code "229") (name "unconnected-(SV5-Pad21)") (class "Default")
      (node (ref "SV5") (pin "21") (pinfunction "21_21") (pintype "passive"))
    )
    (net (code "230") (name "unconnected-(SV5-Pad23)") (class "Default")
      (node (ref "SV5") (pin "23") (pinfunction "23_23") (pintype "passive"))
    )
    (net (code "231") (name "unconnected-(SV5-Pad24)") (class "Default")
      (node (ref "SV5") (pin "24") (pinfunction "24_24") (pintype "passive"))
    )
    (net (code "232") (name "unconnected-(SV5-Pad25)") (class "Default")
      (node (ref "SV5") (pin "25") (pinfunction "25_25") (pintype "passive"))
    )
    (net (code "233") (name "unconnected-(SV5-Pad26)") (class "Default")
      (node (ref "SV5") (pin "26") (pinfunction "26_26") (pintype "passive"))
    )
    (net (code "234") (name "unconnected-(SV5-Pad27)") (class "Default")
      (node (ref "SV5") (pin "27") (pinfunction "27_27") (pintype "passive"))
    )
    (net (code "235") (name "unconnected-(SV5-Pad28)") (class "Default")
      (node (ref "SV5") (pin "28") (pinfunction "28_28") (pintype "passive"))
    )
    (net (code "236") (name "unconnected-(SV5-Pad29)") (class "Default")
      (node (ref "SV5") (pin "29") (pinfunction "29_29") (pintype "passive"))
    )
    (net (code "237") (name "unconnected-(SV5-Pad30)") (class "Default")
      (node (ref "SV5") (pin "30") (pinfunction "30_30") (pintype "passive"))
    )
    (net (code "238") (name "unconnected-(SV5-Pad31)") (class "Default")
      (node (ref "SV5") (pin "31") (pinfunction "31_31") (pintype "passive"))
    )
    (net (code "239") (name "unconnected-(SV5-Pad33)") (class "Default")
      (node (ref "SV5") (pin "33") (pinfunction "33_33") (pintype "passive"))
    )
    (net (code "240") (name "unconnected-(SV5-Pad35)") (class "Default")
      (node (ref "SV5") (pin "35") (pinfunction "35_35") (pintype "passive"))
    )
    (net (code "241") (name "unconnected-(SV5-Pad36)") (class "Default")
      (node (ref "SV5") (pin "36") (pinfunction "36_36") (pintype "passive"))
    )
    (net (code "242") (name "unconnected-(SV5-Pad38)") (class "Default")
      (node (ref "SV5") (pin "38") (pinfunction "38_38") (pintype "passive"))
    )
    (net (code "243") (name "unconnected-(SV5-Pad43)") (class "Default")
      (node (ref "SV5") (pin "43") (pinfunction "43_43") (pintype "passive"))
    )
    (net (code "244") (name "unconnected-(SV5-Pad44)") (class "Default")
      (node (ref "SV5") (pin "44") (pinfunction "44_44") (pintype "passive"))
    )
    (net (code "245") (name "unconnected-(SV5-Pad45)") (class "Default")
      (node (ref "SV5") (pin "45") (pinfunction "45_45") (pintype "passive"))
    )
    (net (code "246") (name "unconnected-(SV5-Pad46)") (class "Default")
      (node (ref "SV5") (pin "46") (pinfunction "46_46") (pintype "passive"))
    )
    (net (code "247") (name "unconnected-(SV5-Pad47)") (class "Default")
      (node (ref "SV5") (pin "47") (pinfunction "47_47") (pintype "passive"))
    )
    (net (code "248") (name "unconnected-(SV5-Pad48)") (class "Default")
      (node (ref "SV5") (pin "48") (pinfunction "48_48") (pintype "passive"))
    )
  )
)
